# PL_DDR.net
KiCad netlist of a schematic drawn in Altium Designer
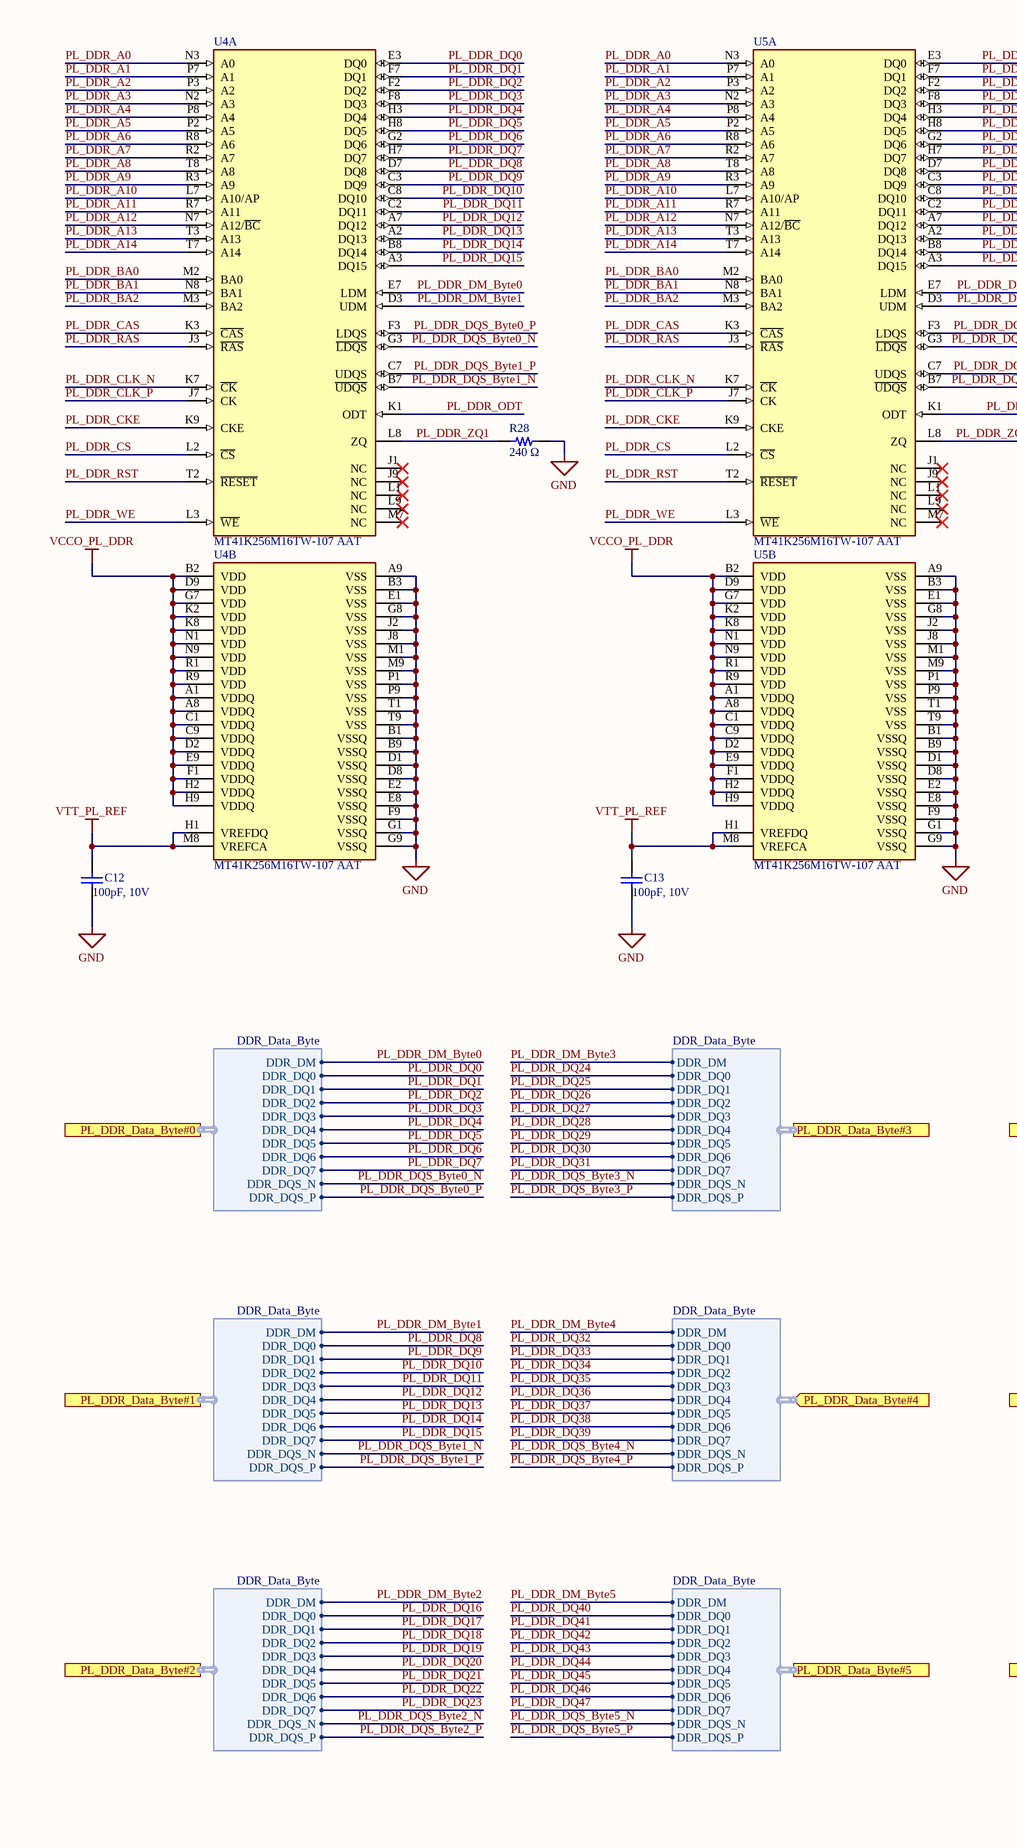
[diagram p0: PL_DDR.SchDoc, left]
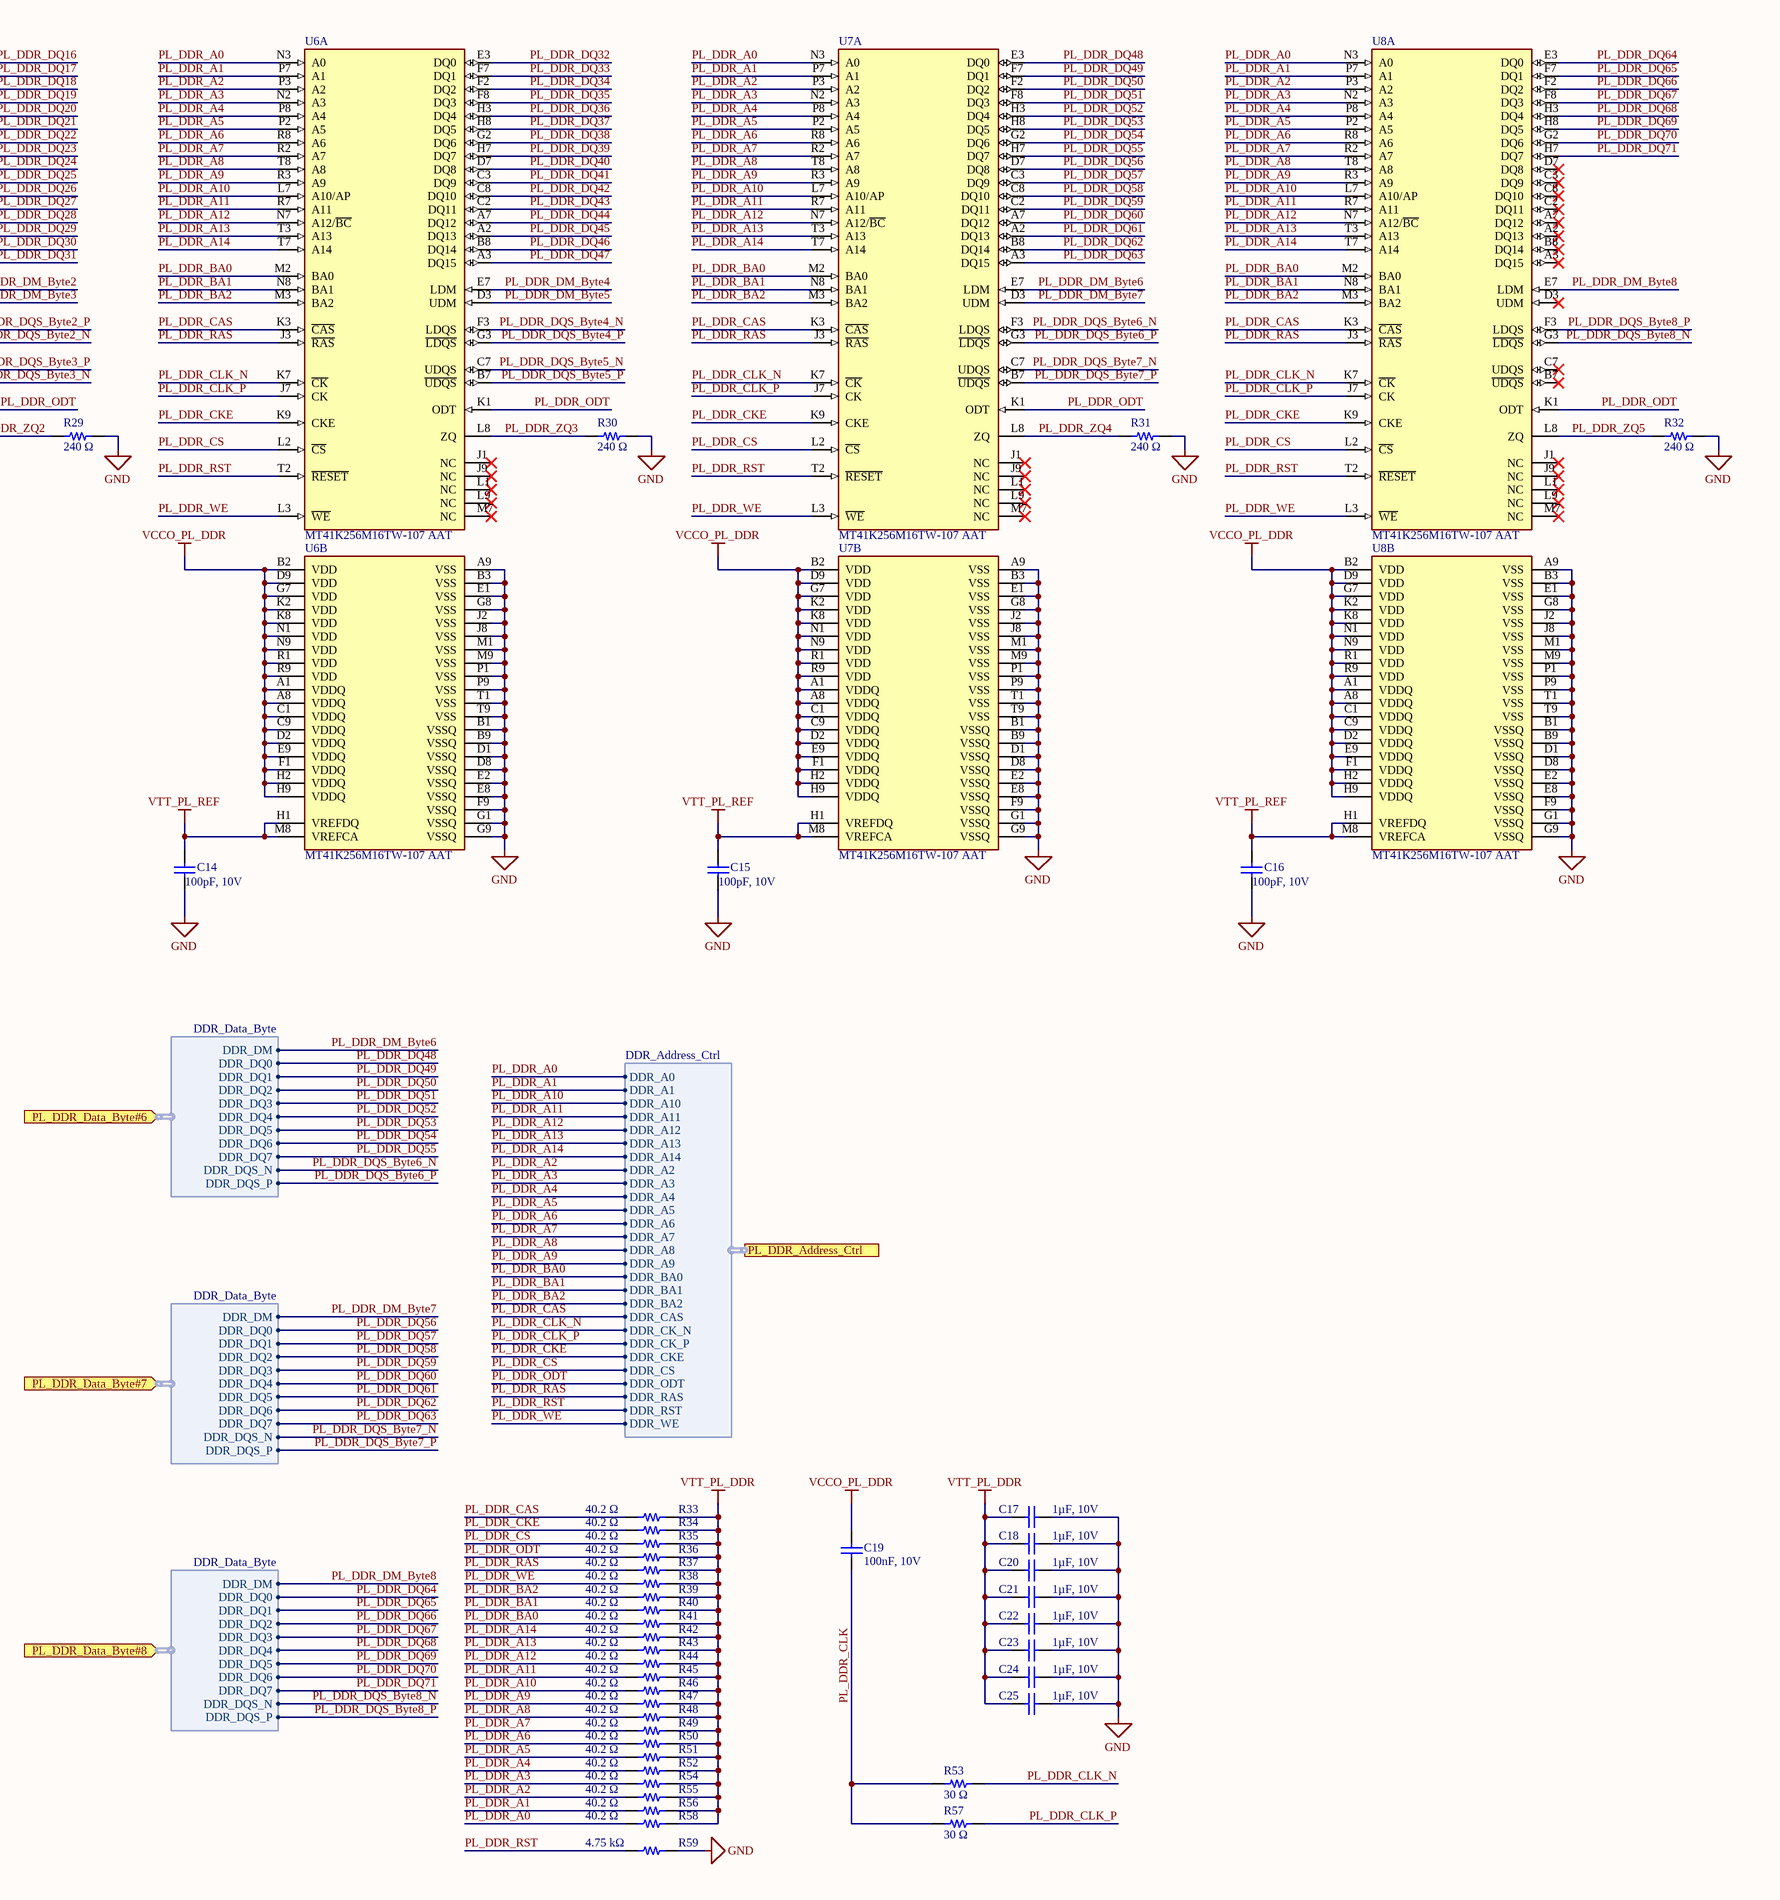
[diagram p1: PL_DDR.SchDoc, right]

(export (version "E")
  (design (tool "Eeschema 10.0.6"))
  (components
    (comp (ref "C12")
      (value "100pF, 10V")
      (footprint "WURTH_WCAP-CSGP_0402")
      (description "WCAP-CSGP Multilayer Ceramic Chip Capacitor, General Purpose, size 0402, NP0, 100pF, 10V")
      (fields
        (field (name "MANUFACTURER PART NUMBER") "885012005013")
        (field (name "MANUFACTURER") "Wurth Elektronik")
      )
      (libsource (lib "SpaceVNXBaseBoard") (part "885012005013"))
    )
    (comp (ref "C13")
      (value "100pF, 10V")
      (footprint "WURTH_WCAP-CSGP_0402")
      (description "WCAP-CSGP Multilayer Ceramic Chip Capacitor, General Purpose, size 0402, NP0, 100pF, 10V")
      (fields
        (field (name "MANUFACTURER PART NUMBER") "885012005013")
        (field (name "MANUFACTURER") "Wurth Elektronik")
      )
      (libsource (lib "SpaceVNXBaseBoard") (part "885012005013"))
    )
    (comp (ref "C14")
      (value "100pF, 10V")
      (footprint "WURTH_WCAP-CSGP_0402")
      (description "WCAP-CSGP Multilayer Ceramic Chip Capacitor, General Purpose, size 0402, NP0, 100pF, 10V")
      (fields
        (field (name "MANUFACTURER PART NUMBER") "885012005013")
        (field (name "MANUFACTURER") "Wurth Elektronik")
      )
      (libsource (lib "SpaceVNXBaseBoard") (part "885012005013"))
    )
    (comp (ref "C15")
      (value "100pF, 10V")
      (footprint "WURTH_WCAP-CSGP_0402")
      (description "WCAP-CSGP Multilayer Ceramic Chip Capacitor, General Purpose, size 0402, NP0, 100pF, 10V")
      (fields
        (field (name "MANUFACTURER PART NUMBER") "885012005013")
        (field (name "MANUFACTURER") "Wurth Elektronik")
      )
      (libsource (lib "SpaceVNXBaseBoard") (part "885012005013"))
    )
    (comp (ref "C16")
      (value "100pF, 10V")
      (footprint "WURTH_WCAP-CSGP_0402")
      (description "WCAP-CSGP Multilayer Ceramic Chip Capacitor, General Purpose, size 0402, NP0, 100pF, 10V")
      (fields
        (field (name "MANUFACTURER PART NUMBER") "885012005013")
        (field (name "MANUFACTURER") "Wurth Elektronik")
      )
      (libsource (lib "SpaceVNXBaseBoard") (part "885012005013"))
    )
    (comp (ref "C17")
      (value "1µF, 10V")
      (footprint "WURTH_WCAP-CSGP_0402")
      (description "WCAP-CSGP Multilayer Ceramic Chip Capacitor, General Purpose, size 0402, X5R, 1uF, 10V")
      (fields
        (field (name "MANUFACTURER PART NUMBER") "885012105012")
        (field (name "MANUFACTURER") "Wurth Elektronik")
      )
      (libsource (lib "SpaceVNXBaseBoard") (part "885012105012"))
    )
    (comp (ref "C18")
      (value "1µF, 10V")
      (footprint "WURTH_WCAP-CSGP_0402")
      (description "WCAP-CSGP Multilayer Ceramic Chip Capacitor, General Purpose, size 0402, X5R, 1uF, 10V")
      (fields
        (field (name "MANUFACTURER PART NUMBER") "885012105012")
        (field (name "MANUFACTURER") "Wurth Elektronik")
      )
      (libsource (lib "SpaceVNXBaseBoard") (part "885012105012"))
    )
    (comp (ref "C19")
      (value "100nF, 10V")
      (footprint "WURTH_WCAP-CSGP_0402")
      (description "WCAP-CSGP Multilayer Ceramic Chip Capacitor, General Purpose, size 0402, X7R, 100nF, 10V")
      (fields
        (field (name "MANUFACTURER PART NUMBER") "885012205018")
        (field (name "MANUFACTURER") "Wurth Elektronik")
      )
      (libsource (lib "SpaceVNXBaseBoard") (part "885012205018"))
    )
    (comp (ref "C20")
      (value "1µF, 10V")
      (footprint "WURTH_WCAP-CSGP_0402")
      (description "WCAP-CSGP Multilayer Ceramic Chip Capacitor, General Purpose, size 0402, X5R, 1uF, 10V")
      (fields
        (field (name "MANUFACTURER PART NUMBER") "885012105012")
        (field (name "MANUFACTURER") "Wurth Elektronik")
      )
      (libsource (lib "SpaceVNXBaseBoard") (part "885012105012"))
    )
    (comp (ref "C21")
      (value "1µF, 10V")
      (footprint "WURTH_WCAP-CSGP_0402")
      (description "WCAP-CSGP Multilayer Ceramic Chip Capacitor, General Purpose, size 0402, X5R, 1uF, 10V")
      (fields
        (field (name "MANUFACTURER PART NUMBER") "885012105012")
        (field (name "MANUFACTURER") "Wurth Elektronik")
      )
      (libsource (lib "SpaceVNXBaseBoard") (part "885012105012"))
    )
    (comp (ref "C22")
      (value "1µF, 10V")
      (footprint "WURTH_WCAP-CSGP_0402")
      (description "WCAP-CSGP Multilayer Ceramic Chip Capacitor, General Purpose, size 0402, X5R, 1uF, 10V")
      (fields
        (field (name "MANUFACTURER PART NUMBER") "885012105012")
        (field (name "MANUFACTURER") "Wurth Elektronik")
      )
      (libsource (lib "SpaceVNXBaseBoard") (part "885012105012"))
    )
    (comp (ref "C23")
      (value "1µF, 10V")
      (footprint "WURTH_WCAP-CSGP_0402")
      (description "WCAP-CSGP Multilayer Ceramic Chip Capacitor, General Purpose, size 0402, X5R, 1uF, 10V")
      (fields
        (field (name "MANUFACTURER PART NUMBER") "885012105012")
        (field (name "MANUFACTURER") "Wurth Elektronik")
      )
      (libsource (lib "SpaceVNXBaseBoard") (part "885012105012"))
    )
    (comp (ref "C24")
      (value "1µF, 10V")
      (footprint "WURTH_WCAP-CSGP_0402")
      (description "WCAP-CSGP Multilayer Ceramic Chip Capacitor, General Purpose, size 0402, X5R, 1uF, 10V")
      (fields
        (field (name "MANUFACTURER PART NUMBER") "885012105012")
        (field (name "MANUFACTURER") "Wurth Elektronik")
      )
      (libsource (lib "SpaceVNXBaseBoard") (part "885012105012"))
    )
    (comp (ref "C25")
      (value "1µF, 10V")
      (footprint "WURTH_WCAP-CSGP_0402")
      (description "WCAP-CSGP Multilayer Ceramic Chip Capacitor, General Purpose, size 0402, X5R, 1uF, 10V")
      (fields
        (field (name "MANUFACTURER PART NUMBER") "885012105012")
        (field (name "MANUFACTURER") "Wurth Elektronik")
      )
      (libsource (lib "SpaceVNXBaseBoard") (part "885012105012"))
    )
    (comp (ref "R28")
      (value "240 Ω")
      (footprint "PANASONIC_ERJ2G_0402")
      (description "General Purpose Thick Film Chip Resistors")
      (fields (field (name "MANUFACTURER") "Panasonic"))
      (libsource (lib "SpaceVNXBaseBoard") (part "ERJ2GEJ241X"))
    )
    (comp (ref "R29")
      (value "240 Ω")
      (footprint "PANASONIC_ERJ2G_0402")
      (description "General Purpose Thick Film Chip Resistors")
      (fields (field (name "MANUFACTURER") "Panasonic"))
      (libsource (lib "SpaceVNXBaseBoard") (part "ERJ2GEJ241X"))
    )
    (comp (ref "R30")
      (value "240 Ω")
      (footprint "PANASONIC_ERJ2G_0402")
      (description "General Purpose Thick Film Chip Resistors")
      (fields (field (name "MANUFACTURER") "Panasonic"))
      (libsource (lib "SpaceVNXBaseBoard") (part "ERJ2GEJ241X"))
    )
    (comp (ref "R31")
      (value "240 Ω")
      (footprint "PANASONIC_ERJ2G_0402")
      (description "General Purpose Thick Film Chip Resistors")
      (fields (field (name "MANUFACTURER") "Panasonic"))
      (libsource (lib "SpaceVNXBaseBoard") (part "ERJ2GEJ241X"))
    )
    (comp (ref "R32")
      (value "240 Ω")
      (footprint "PANASONIC_ERJ2G_0402")
      (description "General Purpose Thick Film Chip Resistors")
      (fields (field (name "MANUFACTURER") "Panasonic"))
      (libsource (lib "SpaceVNXBaseBoard") (part "ERJ2GEJ241X"))
    )
    (comp (ref "R33")
      (value "40.2 Ω")
      (footprint "PANASONIC_ERJ2G_0402")
      (description "General Purpose Thick Film Chip Resistors")
      (fields (field (name "MANUFACTURER") "Panasonic"))
      (libsource (lib "SpaceVNXBaseBoard") (part "ERJ2RKF40R2X"))
    )
    (comp (ref "R34")
      (value "40.2 Ω")
      (footprint "PANASONIC_ERJ2G_0402")
      (description "General Purpose Thick Film Chip Resistors")
      (fields (field (name "MANUFACTURER") "Panasonic"))
      (libsource (lib "SpaceVNXBaseBoard") (part "ERJ2RKF40R2X"))
    )
    (comp (ref "R35")
      (value "40.2 Ω")
      (footprint "PANASONIC_ERJ2G_0402")
      (description "General Purpose Thick Film Chip Resistors")
      (fields (field (name "MANUFACTURER") "Panasonic"))
      (libsource (lib "SpaceVNXBaseBoard") (part "ERJ2RKF40R2X"))
    )
    (comp (ref "R36")
      (value "40.2 Ω")
      (footprint "PANASONIC_ERJ2G_0402")
      (description "General Purpose Thick Film Chip Resistors")
      (fields (field (name "MANUFACTURER") "Panasonic"))
      (libsource (lib "SpaceVNXBaseBoard") (part "ERJ2RKF40R2X"))
    )
    (comp (ref "R37")
      (value "40.2 Ω")
      (footprint "PANASONIC_ERJ2G_0402")
      (description "General Purpose Thick Film Chip Resistors")
      (fields (field (name "MANUFACTURER") "Panasonic"))
      (libsource (lib "SpaceVNXBaseBoard") (part "ERJ2RKF40R2X"))
    )
    (comp (ref "R38")
      (value "40.2 Ω")
      (footprint "PANASONIC_ERJ2G_0402")
      (description "General Purpose Thick Film Chip Resistors")
      (fields (field (name "MANUFACTURER") "Panasonic"))
      (libsource (lib "SpaceVNXBaseBoard") (part "ERJ2RKF40R2X"))
    )
    (comp (ref "R39")
      (value "40.2 Ω")
      (footprint "PANASONIC_ERJ2G_0402")
      (description "General Purpose Thick Film Chip Resistors")
      (fields (field (name "MANUFACTURER") "Panasonic"))
      (libsource (lib "SpaceVNXBaseBoard") (part "ERJ2RKF40R2X"))
    )
    (comp (ref "R40")
      (value "40.2 Ω")
      (footprint "PANASONIC_ERJ2G_0402")
      (description "General Purpose Thick Film Chip Resistors")
      (fields (field (name "MANUFACTURER") "Panasonic"))
      (libsource (lib "SpaceVNXBaseBoard") (part "ERJ2RKF40R2X"))
    )
    (comp (ref "R41")
      (value "40.2 Ω")
      (footprint "PANASONIC_ERJ2G_0402")
      (description "General Purpose Thick Film Chip Resistors")
      (fields (field (name "MANUFACTURER") "Panasonic"))
      (libsource (lib "SpaceVNXBaseBoard") (part "ERJ2RKF40R2X"))
    )
    (comp (ref "R42")
      (value "40.2 Ω")
      (footprint "PANASONIC_ERJ2G_0402")
      (description "General Purpose Thick Film Chip Resistors")
      (fields (field (name "MANUFACTURER") "Panasonic"))
      (libsource (lib "SpaceVNXBaseBoard") (part "ERJ2RKF40R2X"))
    )
    (comp (ref "R43")
      (value "40.2 Ω")
      (footprint "PANASONIC_ERJ2G_0402")
      (description "General Purpose Thick Film Chip Resistors")
      (fields (field (name "MANUFACTURER") "Panasonic"))
      (libsource (lib "SpaceVNXBaseBoard") (part "ERJ2RKF40R2X"))
    )
    (comp (ref "R44")
      (value "40.2 Ω")
      (footprint "PANASONIC_ERJ2G_0402")
      (description "General Purpose Thick Film Chip Resistors")
      (fields (field (name "MANUFACTURER") "Panasonic"))
      (libsource (lib "SpaceVNXBaseBoard") (part "ERJ2RKF40R2X"))
    )
    (comp (ref "R45")
      (value "40.2 Ω")
      (footprint "PANASONIC_ERJ2G_0402")
      (description "General Purpose Thick Film Chip Resistors")
      (fields (field (name "MANUFACTURER") "Panasonic"))
      (libsource (lib "SpaceVNXBaseBoard") (part "ERJ2RKF40R2X"))
    )
    (comp (ref "R46")
      (value "40.2 Ω")
      (footprint "PANASONIC_ERJ2G_0402")
      (description "General Purpose Thick Film Chip Resistors")
      (fields (field (name "MANUFACTURER") "Panasonic"))
      (libsource (lib "SpaceVNXBaseBoard") (part "ERJ2RKF40R2X"))
    )
    (comp (ref "R47")
      (value "40.2 Ω")
      (footprint "PANASONIC_ERJ2G_0402")
      (description "General Purpose Thick Film Chip Resistors")
      (fields (field (name "MANUFACTURER") "Panasonic"))
      (libsource (lib "SpaceVNXBaseBoard") (part "ERJ2RKF40R2X"))
    )
    (comp (ref "R48")
      (value "40.2 Ω")
      (footprint "PANASONIC_ERJ2G_0402")
      (description "General Purpose Thick Film Chip Resistors")
      (fields (field (name "MANUFACTURER") "Panasonic"))
      (libsource (lib "SpaceVNXBaseBoard") (part "ERJ2RKF40R2X"))
    )
    (comp (ref "R49")
      (value "40.2 Ω")
      (footprint "PANASONIC_ERJ2G_0402")
      (description "General Purpose Thick Film Chip Resistors")
      (fields (field (name "MANUFACTURER") "Panasonic"))
      (libsource (lib "SpaceVNXBaseBoard") (part "ERJ2RKF40R2X"))
    )
    (comp (ref "R50")
      (value "40.2 Ω")
      (footprint "PANASONIC_ERJ2G_0402")
      (description "General Purpose Thick Film Chip Resistors")
      (fields (field (name "MANUFACTURER") "Panasonic"))
      (libsource (lib "SpaceVNXBaseBoard") (part "ERJ2RKF40R2X"))
    )
    (comp (ref "R51")
      (value "40.2 Ω")
      (footprint "PANASONIC_ERJ2G_0402")
      (description "General Purpose Thick Film Chip Resistors")
      (fields (field (name "MANUFACTURER") "Panasonic"))
      (libsource (lib "SpaceVNXBaseBoard") (part "ERJ2RKF40R2X"))
    )
    (comp (ref "R52")
      (value "40.2 Ω")
      (footprint "PANASONIC_ERJ2G_0402")
      (description "General Purpose Thick Film Chip Resistors")
      (fields (field (name "MANUFACTURER") "Panasonic"))
      (libsource (lib "SpaceVNXBaseBoard") (part "ERJ2RKF40R2X"))
    )
    (comp (ref "R53")
      (value "30 Ω")
      (footprint "PANASONIC_ERJ2G_0402")
      (description "General Purpose Thick Film Chip Resistors")
      (fields (field (name "MANUFACTURER") "Panasonic"))
      (libsource (lib "SpaceVNXBaseBoard") (part "ERJ2GEJ300X"))
    )
    (comp (ref "R54")
      (value "40.2 Ω")
      (footprint "PANASONIC_ERJ2G_0402")
      (description "General Purpose Thick Film Chip Resistors")
      (fields (field (name "MANUFACTURER") "Panasonic"))
      (libsource (lib "SpaceVNXBaseBoard") (part "ERJ2RKF40R2X"))
    )
    (comp (ref "R55")
      (value "40.2 Ω")
      (footprint "PANASONIC_ERJ2G_0402")
      (description "General Purpose Thick Film Chip Resistors")
      (fields (field (name "MANUFACTURER") "Panasonic"))
      (libsource (lib "SpaceVNXBaseBoard") (part "ERJ2RKF40R2X"))
    )
    (comp (ref "R56")
      (value "40.2 Ω")
      (footprint "PANASONIC_ERJ2G_0402")
      (description "General Purpose Thick Film Chip Resistors")
      (fields (field (name "MANUFACTURER") "Panasonic"))
      (libsource (lib "SpaceVNXBaseBoard") (part "ERJ2RKF40R2X"))
    )
    (comp (ref "R57")
      (value "30 Ω")
      (footprint "PANASONIC_ERJ2G_0402")
      (description "General Purpose Thick Film Chip Resistors")
      (fields (field (name "MANUFACTURER") "Panasonic"))
      (libsource (lib "SpaceVNXBaseBoard") (part "ERJ2GEJ300X"))
    )
    (comp (ref "R58")
      (value "40.2 Ω")
      (footprint "PANASONIC_ERJ2G_0402")
      (description "General Purpose Thick Film Chip Resistors")
      (fields (field (name "MANUFACTURER") "Panasonic"))
      (libsource (lib "SpaceVNXBaseBoard") (part "ERJ2RKF40R2X"))
    )
    (comp (ref "R59")
      (value "4.75 kΩ")
      (footprint "PANASONIC_ERJ2G_0402")
      (description "General Purpose Thick Film Chip Resistors")
      (fields (field (name "MANUFACTURER") "Panasonic"))
      (libsource (lib "SpaceVNXBaseBoard") (part "ERJ2RKF4751X"))
    )
    (comp (ref "U4")
      (value "MT41K256M16TW-107 AAT")
      (footprint "Micron_TW")
      (description "DDR3L SDRAM")
      (libsource (lib "SpaceVNXBaseBoard") (part "MT41K256M16TW-107 AAT"))
    )
    (comp (ref "U5")
      (value "MT41K256M16TW-107 AAT")
      (footprint "Micron_TW")
      (description "DDR3L SDRAM")
      (libsource (lib "SpaceVNXBaseBoard") (part "MT41K256M16TW-107 AAT"))
    )
    (comp (ref "U6")
      (value "MT41K256M16TW-107 AAT")
      (footprint "Micron_TW")
      (description "DDR3L SDRAM")
      (libsource (lib "SpaceVNXBaseBoard") (part "MT41K256M16TW-107 AAT"))
    )
    (comp (ref "U7")
      (value "MT41K256M16TW-107 AAT")
      (footprint "Micron_TW")
      (description "DDR3L SDRAM")
      (libsource (lib "SpaceVNXBaseBoard") (part "MT41K256M16TW-107 AAT"))
    )
    (comp (ref "U8")
      (value "MT41K256M16TW-107 AAT")
      (footprint "Micron_TW")
      (description "DDR3L SDRAM")
      (libsource (lib "SpaceVNXBaseBoard") (part "MT41K256M16TW-107 AAT"))
    )
  )
  (nets
    (net (code "3") (name "/PL_DDR_A0") (class "Default")
      (node (ref "R58") (pin "1") (pinfunction "1_1") (pintype "passive"))
      (node (ref "U4") (pin "N3") (pinfunction "A0_N3") (pintype "input"))
      (node (ref "U5") (pin "N3") (pinfunction "A0_N3") (pintype "input"))
      (node (ref "U6") (pin "N3") (pinfunction "A0_N3") (pintype "input"))
      (node (ref "U7") (pin "N3") (pinfunction "A0_N3") (pintype "input"))
      (node (ref "U8") (pin "N3") (pinfunction "A0_N3") (pintype "input"))
    )
    (net (code "4") (name "/PL_DDR_A1") (class "Default")
      (node (ref "R56") (pin "1") (pinfunction "1_1") (pintype "passive"))
      (node (ref "U4") (pin "P7") (pinfunction "A1_P7") (pintype "input"))
      (node (ref "U5") (pin "P7") (pinfunction "A1_P7") (pintype "input"))
      (node (ref "U6") (pin "P7") (pinfunction "A1_P7") (pintype "input"))
      (node (ref "U7") (pin "P7") (pinfunction "A1_P7") (pintype "input"))
      (node (ref "U8") (pin "P7") (pinfunction "A1_P7") (pintype "input"))
    )
    (net (code "5") (name "/PL_DDR_A2") (class "Default")
      (node (ref "R55") (pin "1") (pinfunction "1_1") (pintype "passive"))
      (node (ref "U4") (pin "P3") (pinfunction "A2_P3") (pintype "input"))
      (node (ref "U5") (pin "P3") (pinfunction "A2_P3") (pintype "input"))
      (node (ref "U6") (pin "P3") (pinfunction "A2_P3") (pintype "input"))
      (node (ref "U7") (pin "P3") (pinfunction "A2_P3") (pintype "input"))
      (node (ref "U8") (pin "P3") (pinfunction "A2_P3") (pintype "input"))
    )
    (net (code "6") (name "/PL_DDR_A3") (class "Default")
      (node (ref "R54") (pin "1") (pinfunction "1_1") (pintype "passive"))
      (node (ref "U4") (pin "N2") (pinfunction "A3_N2") (pintype "input"))
      (node (ref "U5") (pin "N2") (pinfunction "A3_N2") (pintype "input"))
      (node (ref "U6") (pin "N2") (pinfunction "A3_N2") (pintype "input"))
      (node (ref "U7") (pin "N2") (pinfunction "A3_N2") (pintype "input"))
      (node (ref "U8") (pin "N2") (pinfunction "A3_N2") (pintype "input"))
    )
    (net (code "7") (name "/PL_DDR_A4") (class "Default")
      (node (ref "R52") (pin "1") (pinfunction "1_1") (pintype "passive"))
      (node (ref "U4") (pin "P8") (pinfunction "A4_P8") (pintype "input"))
      (node (ref "U5") (pin "P8") (pinfunction "A4_P8") (pintype "input"))
      (node (ref "U6") (pin "P8") (pinfunction "A4_P8") (pintype "input"))
      (node (ref "U7") (pin "P8") (pinfunction "A4_P8") (pintype "input"))
      (node (ref "U8") (pin "P8") (pinfunction "A4_P8") (pintype "input"))
    )
    (net (code "8") (name "/PL_DDR_A5") (class "Default")
      (node (ref "R51") (pin "1") (pinfunction "1_1") (pintype "passive"))
      (node (ref "U4") (pin "P2") (pinfunction "A5_P2") (pintype "input"))
      (node (ref "U5") (pin "P2") (pinfunction "A5_P2") (pintype "input"))
      (node (ref "U6") (pin "P2") (pinfunction "A5_P2") (pintype "input"))
      (node (ref "U7") (pin "P2") (pinfunction "A5_P2") (pintype "input"))
      (node (ref "U8") (pin "P2") (pinfunction "A5_P2") (pintype "input"))
    )
    (net (code "9") (name "/PL_DDR_A6") (class "Default")
      (node (ref "R50") (pin "1") (pinfunction "1_1") (pintype "passive"))
      (node (ref "U4") (pin "R8") (pinfunction "A6_R8") (pintype "input"))
      (node (ref "U5") (pin "R8") (pinfunction "A6_R8") (pintype "input"))
      (node (ref "U6") (pin "R8") (pinfunction "A6_R8") (pintype "input"))
      (node (ref "U7") (pin "R8") (pinfunction "A6_R8") (pintype "input"))
      (node (ref "U8") (pin "R8") (pinfunction "A6_R8") (pintype "input"))
    )
    (net (code "10") (name "/PL_DDR_A7") (class "Default")
      (node (ref "R49") (pin "1") (pinfunction "1_1") (pintype "passive"))
      (node (ref "U4") (pin "R2") (pinfunction "A7_R2") (pintype "input"))
      (node (ref "U5") (pin "R2") (pinfunction "A7_R2") (pintype "input"))
      (node (ref "U6") (pin "R2") (pinfunction "A7_R2") (pintype "input"))
      (node (ref "U7") (pin "R2") (pinfunction "A7_R2") (pintype "input"))
      (node (ref "U8") (pin "R2") (pinfunction "A7_R2") (pintype "input"))
    )
    (net (code "11") (name "/PL_DDR_A8") (class "Default")
      (node (ref "R48") (pin "1") (pinfunction "1_1") (pintype "passive"))
      (node (ref "U4") (pin "T8") (pinfunction "A8_T8") (pintype "input"))
      (node (ref "U5") (pin "T8") (pinfunction "A8_T8") (pintype "input"))
      (node (ref "U6") (pin "T8") (pinfunction "A8_T8") (pintype "input"))
      (node (ref "U7") (pin "T8") (pinfunction "A8_T8") (pintype "input"))
      (node (ref "U8") (pin "T8") (pinfunction "A8_T8") (pintype "input"))
    )
    (net (code "12") (name "/PL_DDR_A9") (class "Default")
      (node (ref "R47") (pin "1") (pinfunction "1_1") (pintype "passive"))
      (node (ref "U4") (pin "R3") (pinfunction "A9_R3") (pintype "input"))
      (node (ref "U5") (pin "R3") (pinfunction "A9_R3") (pintype "input"))
      (node (ref "U6") (pin "R3") (pinfunction "A9_R3") (pintype "input"))
      (node (ref "U7") (pin "R3") (pinfunction "A9_R3") (pintype "input"))
      (node (ref "U8") (pin "R3") (pinfunction "A9_R3") (pintype "input"))
    )
    (net (code "13") (name "/PL_DDR_A10") (class "Default")
      (node (ref "R46") (pin "1") (pinfunction "1_1") (pintype "passive"))
      (node (ref "U4") (pin "L7") (pinfunction "A10/AP_L7") (pintype "input"))
      (node (ref "U5") (pin "L7") (pinfunction "A10/AP_L7") (pintype "input"))
      (node (ref "U6") (pin "L7") (pinfunction "A10/AP_L7") (pintype "input"))
      (node (ref "U7") (pin "L7") (pinfunction "A10/AP_L7") (pintype "input"))
      (node (ref "U8") (pin "L7") (pinfunction "A10/AP_L7") (pintype "input"))
    )
    (net (code "14") (name "/PL_DDR_A11") (class "Default")
      (node (ref "R45") (pin "1") (pinfunction "1_1") (pintype "passive"))
      (node (ref "U4") (pin "R7") (pinfunction "A11_R7") (pintype "input"))
      (node (ref "U5") (pin "R7") (pinfunction "A11_R7") (pintype "input"))
      (node (ref "U6") (pin "R7") (pinfunction "A11_R7") (pintype "input"))
      (node (ref "U7") (pin "R7") (pinfunction "A11_R7") (pintype "input"))
      (node (ref "U8") (pin "R7") (pinfunction "A11_R7") (pintype "input"))
    )
    (net (code "15") (name "/PL_DDR_A12") (class "Default")
      (node (ref "R44") (pin "1") (pinfunction "1_1") (pintype "passive"))
      (node (ref "U4") (pin "N7") (pinfunction "A12/~{BC}_N7") (pintype "input"))
      (node (ref "U5") (pin "N7") (pinfunction "A12/~{BC}_N7") (pintype "input"))
      (node (ref "U6") (pin "N7") (pinfunction "A12/~{BC}_N7") (pintype "input"))
      (node (ref "U7") (pin "N7") (pinfunction "A12/~{BC}_N7") (pintype "input"))
      (node (ref "U8") (pin "N7") (pinfunction "A12/~{BC}_N7") (pintype "input"))
    )
    (net (code "16") (name "/PL_DDR_A13") (class "Default")
      (node (ref "R43") (pin "1") (pinfunction "1_1") (pintype "passive"))
      (node (ref "U4") (pin "T3") (pinfunction "A13_T3") (pintype "input"))
      (node (ref "U5") (pin "T3") (pinfunction "A13_T3") (pintype "input"))
      (node (ref "U6") (pin "T3") (pinfunction "A13_T3") (pintype "input"))
      (node (ref "U7") (pin "T3") (pinfunction "A13_T3") (pintype "input"))
      (node (ref "U8") (pin "T3") (pinfunction "A13_T3") (pintype "input"))
    )
    (net (code "17") (name "/PL_DDR_A14") (class "Default")
      (node (ref "R42") (pin "1") (pinfunction "1_1") (pintype "passive"))
      (node (ref "U4") (pin "T7") (pinfunction "A14_T7") (pintype "input"))
      (node (ref "U5") (pin "T7") (pinfunction "A14_T7") (pintype "input"))
      (node (ref "U6") (pin "T7") (pinfunction "A14_T7") (pintype "input"))
      (node (ref "U7") (pin "T7") (pinfunction "A14_T7") (pintype "input"))
      (node (ref "U8") (pin "T7") (pinfunction "A14_T7") (pintype "input"))
    )
    (net (code "18") (name "/PL_DDR_BA0") (class "Default")
      (node (ref "R41") (pin "1") (pinfunction "1_1") (pintype "passive"))
      (node (ref "U4") (pin "M2") (pinfunction "BA0_M2") (pintype "input"))
      (node (ref "U5") (pin "M2") (pinfunction "BA0_M2") (pintype "input"))
      (node (ref "U6") (pin "M2") (pinfunction "BA0_M2") (pintype "input"))
      (node (ref "U7") (pin "M2") (pinfunction "BA0_M2") (pintype "input"))
      (node (ref "U8") (pin "M2") (pinfunction "BA0_M2") (pintype "input"))
    )
    (net (code "19") (name "/PL_DDR_BA1") (class "Default")
      (node (ref "R40") (pin "1") (pinfunction "1_1") (pintype "passive"))
      (node (ref "U4") (pin "N8") (pinfunction "BA1_N8") (pintype "input"))
      (node (ref "U5") (pin "N8") (pinfunction "BA1_N8") (pintype "input"))
      (node (ref "U6") (pin "N8") (pinfunction "BA1_N8") (pintype "input"))
      (node (ref "U7") (pin "N8") (pinfunction "BA1_N8") (pintype "input"))
      (node (ref "U8") (pin "N8") (pinfunction "BA1_N8") (pintype "input"))
    )
    (net (code "20") (name "/PL_DDR_BA2") (class "Default")
      (node (ref "R39") (pin "1") (pinfunction "1_1") (pintype "passive"))
      (node (ref "U4") (pin "M3") (pinfunction "BA2_M3") (pintype "input"))
      (node (ref "U5") (pin "M3") (pinfunction "BA2_M3") (pintype "input"))
      (node (ref "U6") (pin "M3") (pinfunction "BA2_M3") (pintype "input"))
      (node (ref "U7") (pin "M3") (pinfunction "BA2_M3") (pintype "input"))
      (node (ref "U8") (pin "M3") (pinfunction "BA2_M3") (pintype "input"))
    )
    (net (code "21") (name "/PL_DDR_CAS") (class "Default")
      (node (ref "R33") (pin "1") (pinfunction "1_1") (pintype "passive"))
      (node (ref "U4") (pin "K3") (pinfunction "~{CAS}_K3") (pintype "input"))
      (node (ref "U5") (pin "K3") (pinfunction "~{CAS}_K3") (pintype "input"))
      (node (ref "U6") (pin "K3") (pinfunction "~{CAS}_K3") (pintype "input"))
      (node (ref "U7") (pin "K3") (pinfunction "~{CAS}_K3") (pintype "input"))
      (node (ref "U8") (pin "K3") (pinfunction "~{CAS}_K3") (pintype "input"))
    )
    (net (code "22") (name "/PL_DDR_CKE") (class "Default")
      (node (ref "R34") (pin "1") (pinfunction "1_1") (pintype "passive"))
      (node (ref "U4") (pin "K9") (pinfunction "CKE_K9") (pintype "input"))
      (node (ref "U5") (pin "K9") (pinfunction "CKE_K9") (pintype "input"))
      (node (ref "U6") (pin "K9") (pinfunction "CKE_K9") (pintype "input"))
      (node (ref "U7") (pin "K9") (pinfunction "CKE_K9") (pintype "input"))
      (node (ref "U8") (pin "K9") (pinfunction "CKE_K9") (pintype "input"))
    )
    (net (code "23") (name "/PL_DDR_CLK") (class "Default")
      (node (ref "C19") (pin "1") (pinfunction "1_1") (pintype "passive"))
      (node (ref "R53") (pin "2") (pinfunction "2_2") (pintype "passive"))
      (node (ref "R57") (pin "2") (pinfunction "2_2") (pintype "passive"))
    )
    (net (code "24") (name "/PL_DDR_CLK_N") (class "Default")
      (node (ref "R53") (pin "1") (pinfunction "1_1") (pintype "passive"))
      (node (ref "U4") (pin "K7") (pinfunction "~{CK}_K7") (pintype "input"))
      (node (ref "U5") (pin "K7") (pinfunction "~{CK}_K7") (pintype "input"))
      (node (ref "U6") (pin "K7") (pinfunction "~{CK}_K7") (pintype "input"))
      (node (ref "U7") (pin "K7") (pinfunction "~{CK}_K7") (pintype "input"))
      (node (ref "U8") (pin "K7") (pinfunction "~{CK}_K7") (pintype "input"))
    )
    (net (code "25") (name "/PL_DDR_CLK_P") (class "Default")
      (node (ref "R57") (pin "1") (pinfunction "1_1") (pintype "passive"))
      (node (ref "U4") (pin "J7") (pinfunction "CK_J7") (pintype "input"))
      (node (ref "U5") (pin "J7") (pinfunction "CK_J7") (pintype "input"))
      (node (ref "U6") (pin "J7") (pinfunction "CK_J7") (pintype "input"))
      (node (ref "U7") (pin "J7") (pinfunction "CK_J7") (pintype "input"))
      (node (ref "U8") (pin "J7") (pinfunction "CK_J7") (pintype "input"))
    )
    (net (code "26") (name "/PL_DDR_CS") (class "Default")
      (node (ref "R35") (pin "1") (pinfunction "1_1") (pintype "passive"))
      (node (ref "U4") (pin "L2") (pinfunction "~{CS}_L2") (pintype "input"))
      (node (ref "U5") (pin "L2") (pinfunction "~{CS}_L2") (pintype "input"))
      (node (ref "U6") (pin "L2") (pinfunction "~{CS}_L2") (pintype "input"))
      (node (ref "U7") (pin "L2") (pinfunction "~{CS}_L2") (pintype "input"))
      (node (ref "U8") (pin "L2") (pinfunction "~{CS}_L2") (pintype "input"))
    )
    (net (code "27") (name "/PL_DDR_DM_Byte0") (class "Default")
      (node (ref "U4") (pin "E7") (pinfunction "LDM_E7") (pintype "input"))
    )
    (net (code "28") (name "/PL_DDR_DM_Byte1") (class "Default")
      (node (ref "U4") (pin "D3") (pinfunction "UDM_D3") (pintype "input"))
    )
    (net (code "29") (name "/PL_DDR_DM_Byte2") (class "Default")
      (node (ref "U5") (pin "E7") (pinfunction "LDM_E7") (pintype "input"))
    )
    (net (code "30") (name "/PL_DDR_DM_Byte3") (class "Default")
      (node (ref "U5") (pin "D3") (pinfunction "UDM_D3") (pintype "input"))
    )
    (net (code "31") (name "/PL_DDR_DM_Byte4") (class "Default")
      (node (ref "U6") (pin "E7") (pinfunction "LDM_E7") (pintype "input"))
    )
    (net (code "32") (name "/PL_DDR_DM_Byte5") (class "Default")
      (node (ref "U6") (pin "D3") (pinfunction "UDM_D3") (pintype "input"))
    )
    (net (code "33") (name "/PL_DDR_DM_Byte6") (class "Default")
      (node (ref "U7") (pin "E7") (pinfunction "LDM_E7") (pintype "input"))
    )
    (net (code "34") (name "/PL_DDR_DM_Byte7") (class "Default")
      (node (ref "U7") (pin "D3") (pinfunction "UDM_D3") (pintype "input"))
    )
    (net (code "35") (name "/PL_DDR_DM_Byte8") (class "Default")
      (node (ref "U8") (pin "E7") (pinfunction "LDM_E7") (pintype "input"))
    )
    (net (code "36") (name "/PL_DDR_DQ0") (class "Default")
      (node (ref "U4") (pin "E3") (pinfunction "DQ0_E3") (pintype "bidirectional"))
    )
    (net (code "37") (name "/PL_DDR_DQ1") (class "Default")
      (node (ref "U4") (pin "F7") (pinfunction "DQ1_F7") (pintype "bidirectional"))
    )
    (net (code "38") (name "/PL_DDR_DQ2") (class "Default")
      (node (ref "U4") (pin "F2") (pinfunction "DQ2_F2") (pintype "bidirectional"))
    )
    (net (code "39") (name "/PL_DDR_DQ3") (class "Default")
      (node (ref "U4") (pin "F8") (pinfunction "DQ3_F8") (pintype "bidirectional"))
    )
    (net (code "40") (name "/PL_DDR_DQ4") (class "Default")
      (node (ref "U4") (pin "H3") (pinfunction "DQ4_H3") (pintype "bidirectional"))
    )
    (net (code "41") (name "/PL_DDR_DQ5") (class "Default")
      (node (ref "U4") (pin "H8") (pinfunction "DQ5_H8") (pintype "bidirectional"))
    )
    (net (code "42") (name "/PL_DDR_DQ6") (class "Default")
      (node (ref "U4") (pin "G2") (pinfunction "DQ6_G2") (pintype "bidirectional"))
    )
    (net (code "43") (name "/PL_DDR_DQ7") (class "Default")
      (node (ref "U4") (pin "H7") (pinfunction "DQ7_H7") (pintype "bidirectional"))
    )
    (net (code "44") (name "/PL_DDR_DQ8") (class "Default")
      (node (ref "U4") (pin "D7") (pinfunction "DQ8_D7") (pintype "bidirectional"))
    )
    (net (code "45") (name "/PL_DDR_DQ9") (class "Default")
      (node (ref "U4") (pin "C3") (pinfunction "DQ9_C3") (pintype "bidirectional"))
    )
    (net (code "46") (name "/PL_DDR_DQ10") (class "Default")
      (node (ref "U4") (pin "C8") (pinfunction "DQ10_C8") (pintype "bidirectional"))
    )
    (net (code "47") (name "/PL_DDR_DQ11") (class "Default")
      (node (ref "U4") (pin "C2") (pinfunction "DQ11_C2") (pintype "bidirectional"))
    )
    (net (code "48") (name "/PL_DDR_DQ12") (class "Default")
      (node (ref "U4") (pin "A7") (pinfunction "DQ12_A7") (pintype "bidirectional"))
    )
    (net (code "49") (name "/PL_DDR_DQ13") (class "Default")
      (node (ref "U4") (pin "A2") (pinfunction "DQ13_A2") (pintype "bidirectional"))
    )
    (net (code "50") (name "/PL_DDR_DQ14") (class "Default")
      (node (ref "U4") (pin "B8") (pinfunction "DQ14_B8") (pintype "bidirectional"))
    )
    (net (code "51") (name "/PL_DDR_DQ15") (class "Default")
      (node (ref "U4") (pin "A3") (pinfunction "DQ15_A3") (pintype "bidirectional"))
    )
    (net (code "52") (name "/PL_DDR_DQ16") (class "Default")
      (node (ref "U5") (pin "E3") (pinfunction "DQ0_E3") (pintype "bidirectional"))
    )
    (net (code "53") (name "/PL_DDR_DQ17") (class "Default")
      (node (ref "U5") (pin "F7") (pinfunction "DQ1_F7") (pintype "bidirectional"))
    )
    (net (code "54") (name "/PL_DDR_DQ18") (class "Default")
      (node (ref "U5") (pin "F2") (pinfunction "DQ2_F2") (pintype "bidirectional"))
    )
    (net (code "55") (name "/PL_DDR_DQ19") (class "Default")
      (node (ref "U5") (pin "F8") (pinfunction "DQ3_F8") (pintype "bidirectional"))
    )
    (net (code "56") (name "/PL_DDR_DQ20") (class "Default")
      (node (ref "U5") (pin "H3") (pinfunction "DQ4_H3") (pintype "bidirectional"))
    )
    (net (code "57") (name "/PL_DDR_DQ21") (class "Default")
      (node (ref "U5") (pin "H8") (pinfunction "DQ5_H8") (pintype "bidirectional"))
    )
    (net (code "58") (name "/PL_DDR_DQ22") (class "Default")
      (node (ref "U5") (pin "G2") (pinfunction "DQ6_G2") (pintype "bidirectional"))
    )
    (net (code "59") (name "/PL_DDR_DQ23") (class "Default")
      (node (ref "U5") (pin "H7") (pinfunction "DQ7_H7") (pintype "bidirectional"))
    )
    (net (code "60") (name "/PL_DDR_DQ24") (class "Default")
      (node (ref "U5") (pin "D7") (pinfunction "DQ8_D7") (pintype "bidirectional"))
    )
    (net (code "61") (name "/PL_DDR_DQ25") (class "Default")
      (node (ref "U5") (pin "C3") (pinfunction "DQ9_C3") (pintype "bidirectional"))
    )
    (net (code "62") (name "/PL_DDR_DQ26") (class "Default")
      (node (ref "U5") (pin "C8") (pinfunction "DQ10_C8") (pintype "bidirectional"))
    )
    (net (code "63") (name "/PL_DDR_DQ27") (class "Default")
      (node (ref "U5") (pin "C2") (pinfunction "DQ11_C2") (pintype "bidirectional"))
    )
    (net (code "64") (name "/PL_DDR_DQ28") (class "Default")
      (node (ref "U5") (pin "A7") (pinfunction "DQ12_A7") (pintype "bidirectional"))
    )
    (net (code "65") (name "/PL_DDR_DQ29") (class "Default")
      (node (ref "U5") (pin "A2") (pinfunction "DQ13_A2") (pintype "bidirectional"))
    )
    (net (code "66") (name "/PL_DDR_DQ30") (class "Default")
      (node (ref "U5") (pin "B8") (pinfunction "DQ14_B8") (pintype "bidirectional"))
    )
    (net (code "67") (name "/PL_DDR_DQ31") (class "Default")
      (node (ref "U5") (pin "A3") (pinfunction "DQ15_A3") (pintype "bidirectional"))
    )
    (net (code "68") (name "/PL_DDR_DQ32") (class "Default")
      (node (ref "U6") (pin "E3") (pinfunction "DQ0_E3") (pintype "bidirectional"))
    )
    (net (code "69") (name "/PL_DDR_DQ33") (class "Default")
      (node (ref "U6") (pin "F7") (pinfunction "DQ1_F7") (pintype "bidirectional"))
    )
    (net (code "70") (name "/PL_DDR_DQ34") (class "Default")
      (node (ref "U6") (pin "F2") (pinfunction "DQ2_F2") (pintype "bidirectional"))
    )
    (net (code "71") (name "/PL_DDR_DQ35") (class "Default")
      (node (ref "U6") (pin "F8") (pinfunction "DQ3_F8") (pintype "bidirectional"))
    )
    (net (code "72") (name "/PL_DDR_DQ36") (class "Default")
      (node (ref "U6") (pin "H3") (pinfunction "DQ4_H3") (pintype "bidirectional"))
    )
    (net (code "73") (name "/PL_DDR_DQ37") (class "Default")
      (node (ref "U6") (pin "H8") (pinfunction "DQ5_H8") (pintype "bidirectional"))
    )
    (net (code "74") (name "/PL_DDR_DQ38") (class "Default")
      (node (ref "U6") (pin "G2") (pinfunction "DQ6_G2") (pintype "bidirectional"))
    )
    (net (code "75") (name "/PL_DDR_DQ39") (class "Default")
      (node (ref "U6") (pin "H7") (pinfunction "DQ7_H7") (pintype "bidirectional"))
    )
    (net (code "76") (name "/PL_DDR_DQ40") (class "Default")
      (node (ref "U6") (pin "D7") (pinfunction "DQ8_D7") (pintype "bidirectional"))
    )
    (net (code "77") (name "/PL_DDR_DQ41") (class "Default")
      (node (ref "U6") (pin "C3") (pinfunction "DQ9_C3") (pintype "bidirectional"))
    )
    (net (code "78") (name "/PL_DDR_DQ42") (class "Default")
      (node (ref "U6") (pin "C8") (pinfunction "DQ10_C8") (pintype "bidirectional"))
    )
    (net (code "79") (name "/PL_DDR_DQ43") (class "Default")
      (node (ref "U6") (pin "C2") (pinfunction "DQ11_C2") (pintype "bidirectional"))
    )
    (net (code "80") (name "/PL_DDR_DQ44") (class "Default")
      (node (ref "U6") (pin "A7") (pinfunction "DQ12_A7") (pintype "bidirectional"))
    )
    (net (code "81") (name "/PL_DDR_DQ45") (class "Default")
      (node (ref "U6") (pin "A2") (pinfunction "DQ13_A2") (pintype "bidirectional"))
    )
    (net (code "82") (name "/PL_DDR_DQ46") (class "Default")
      (node (ref "U6") (pin "B8") (pinfunction "DQ14_B8") (pintype "bidirectional"))
    )
    (net (code "83") (name "/PL_DDR_DQ47") (class "Default")
      (node (ref "U6") (pin "A3") (pinfunction "DQ15_A3") (pintype "bidirectional"))
    )
    (net (code "84") (name "/PL_DDR_DQ48") (class "Default")
      (node (ref "U7") (pin "E3") (pinfunction "DQ0_E3") (pintype "bidirectional"))
    )
    (net (code "85") (name "/PL_DDR_DQ49") (class "Default")
      (node (ref "U7") (pin "F7") (pinfunction "DQ1_F7") (pintype "bidirectional"))
    )
    (net (code "86") (name "/PL_DDR_DQ50") (class "Default")
      (node (ref "U7") (pin "F2") (pinfunction "DQ2_F2") (pintype "bidirectional"))
    )
    (net (code "87") (name "/PL_DDR_DQ51") (class "Default")
      (node (ref "U7") (pin "F8") (pinfunction "DQ3_F8") (pintype "bidirectional"))
    )
    (net (code "88") (name "/PL_DDR_DQ52") (class "Default")
      (node (ref "U7") (pin "H3") (pinfunction "DQ4_H3") (pintype "bidirectional"))
    )
    (net (code "89") (name "/PL_DDR_DQ53") (class "Default")
      (node (ref "U7") (pin "H8") (pinfunction "DQ5_H8") (pintype "bidirectional"))
    )
    (net (code "90") (name "/PL_DDR_DQ54") (class "Default")
      (node (ref "U7") (pin "G2") (pinfunction "DQ6_G2") (pintype "bidirectional"))
    )
    (net (code "91") (name "/PL_DDR_DQ55") (class "Default")
      (node (ref "U7") (pin "H7") (pinfunction "DQ7_H7") (pintype "bidirectional"))
    )
    (net (code "92") (name "/PL_DDR_DQ56") (class "Default")
      (node (ref "U7") (pin "D7") (pinfunction "DQ8_D7") (pintype "bidirectional"))
    )
    (net (code "93") (name "/PL_DDR_DQ57") (class "Default")
      (node (ref "U7") (pin "C3") (pinfunction "DQ9_C3") (pintype "bidirectional"))
    )
    (net (code "94") (name "/PL_DDR_DQ58") (class "Default")
      (node (ref "U7") (pin "C8") (pinfunction "DQ10_C8") (pintype "bidirectional"))
    )
    (net (code "95") (name "/PL_DDR_DQ59") (class "Default")
      (node (ref "U7") (pin "C2") (pinfunction "DQ11_C2") (pintype "bidirectional"))
    )
    (net (code "96") (name "/PL_DDR_DQ60") (class "Default")
      (node (ref "U7") (pin "A7") (pinfunction "DQ12_A7") (pintype "bidirectional"))
    )
    (net (code "97") (name "/PL_DDR_DQ61") (class "Default")
      (node (ref "U7") (pin "A2") (pinfunction "DQ13_A2") (pintype "bidirectional"))
    )
    (net (code "98") (name "/PL_DDR_DQ62") (class "Default")
      (node (ref "U7") (pin "B8") (pinfunction "DQ14_B8") (pintype "bidirectional"))
    )
    (net (code "99") (name "/PL_DDR_DQ63") (class "Default")
      (node (ref "U7") (pin "A3") (pinfunction "DQ15_A3") (pintype "bidirectional"))
    )
    (net (code "100") (name "/PL_DDR_DQ64") (class "Default")
      (node (ref "U8") (pin "E3") (pinfunction "DQ0_E3") (pintype "bidirectional"))
    )
    (net (code "101") (name "/PL_DDR_DQ65") (class "Default")
      (node (ref "U8") (pin "F7") (pinfunction "DQ1_F7") (pintype "bidirectional"))
    )
    (net (code "102") (name "/PL_DDR_DQ66") (class "Default")
      (node (ref "U8") (pin "F2") (pinfunction "DQ2_F2") (pintype "bidirectional"))
    )
    (net (code "103") (name "/PL_DDR_DQ67") (class "Default")
      (node (ref "U8") (pin "F8") (pinfunction "DQ3_F8") (pintype "bidirectional"))
    )
    (net (code "104") (name "/PL_DDR_DQ68") (class "Default")
      (node (ref "U8") (pin "H3") (pinfunction "DQ4_H3") (pintype "bidirectional"))
    )
    (net (code "105") (name "/PL_DDR_DQ69") (class "Default")
      (node (ref "U8") (pin "H8") (pinfunction "DQ5_H8") (pintype "bidirectional"))
    )
    (net (code "106") (name "/PL_DDR_DQ70") (class "Default")
      (node (ref "U8") (pin "G2") (pinfunction "DQ6_G2") (pintype "bidirectional"))
    )
    (net (code "107") (name "/PL_DDR_DQ71") (class "Default")
      (node (ref "U8") (pin "H7") (pinfunction "DQ7_H7") (pintype "bidirectional"))
    )
    (net (code "108") (name "/PL_DDR_DQS_Byte0_N") (class "Default")
      (node (ref "U4") (pin "G3") (pinfunction "~{LDQS}_G3") (pintype "bidirectional"))
    )
    (net (code "109") (name "/PL_DDR_DQS_Byte0_P") (class "Default")
      (node (ref "U4") (pin "F3") (pinfunction "LDQS_F3") (pintype "bidirectional"))
    )
    (net (code "110") (name "/PL_DDR_DQS_Byte1_N") (class "Default")
      (node (ref "U4") (pin "B7") (pinfunction "~{UDQS}_B7") (pintype "bidirectional"))
    )
    (net (code "111") (name "/PL_DDR_DQS_Byte1_P") (class "Default")
      (node (ref "U4") (pin "C7") (pinfunction "UDQS_C7") (pintype "bidirectional"))
    )
    (net (code "112") (name "/PL_DDR_DQS_Byte2_N") (class "Default")
      (node (ref "U5") (pin "G3") (pinfunction "~{LDQS}_G3") (pintype "bidirectional"))
    )
    (net (code "113") (name "/PL_DDR_DQS_Byte2_P") (class "Default")
      (node (ref "U5") (pin "F3") (pinfunction "LDQS_F3") (pintype "bidirectional"))
    )
    (net (code "114") (name "/PL_DDR_DQS_Byte3_N") (class "Default")
      (node (ref "U5") (pin "B7") (pinfunction "~{UDQS}_B7") (pintype "bidirectional"))
    )
    (net (code "115") (name "/PL_DDR_DQS_Byte3_P") (class "Default")
      (node (ref "U5") (pin "C7") (pinfunction "UDQS_C7") (pintype "bidirectional"))
    )
    (net (code "116") (name "/PL_DDR_DQS_Byte4_N") (class "Default")
      (node (ref "U6") (pin "F3") (pinfunction "LDQS_F3") (pintype "bidirectional"))
    )
    (net (code "117") (name "/PL_DDR_DQS_Byte4_P") (class "Default")
      (node (ref "U6") (pin "G3") (pinfunction "~{LDQS}_G3") (pintype "bidirectional"))
    )
    (net (code "118") (name "/PL_DDR_DQS_Byte5_N") (class "Default")
      (node (ref "U6") (pin "C7") (pinfunction "UDQS_C7") (pintype "bidirectional"))
    )
    (net (code "119") (name "/PL_DDR_DQS_Byte5_P") (class "Default")
      (node (ref "U6") (pin "B7") (pinfunction "~{UDQS}_B7") (pintype "bidirectional"))
    )
    (net (code "120") (name "/PL_DDR_DQS_Byte6_N") (class "Default")
      (node (ref "U7") (pin "F3") (pinfunction "LDQS_F3") (pintype "bidirectional"))
    )
    (net (code "121") (name "/PL_DDR_DQS_Byte6_P") (class "Default")
      (node (ref "U7") (pin "G3") (pinfunction "~{LDQS}_G3") (pintype "bidirectional"))
    )
    (net (code "122") (name "/PL_DDR_DQS_Byte7_N") (class "Default")
      (node (ref "U7") (pin "C7") (pinfunction "UDQS_C7") (pintype "bidirectional"))
    )
    (net (code "123") (name "/PL_DDR_DQS_Byte7_P") (class "Default")
      (node (ref "U7") (pin "B7") (pinfunction "~{UDQS}_B7") (pintype "bidirectional"))
    )
    (net (code "124") (name "/PL_DDR_DQS_Byte8_N") (class "Default")
      (node (ref "U8") (pin "G3") (pinfunction "~{LDQS}_G3") (pintype "bidirectional"))
    )
    (net (code "125") (name "/PL_DDR_DQS_Byte8_P") (class "Default")
      (node (ref "U8") (pin "F3") (pinfunction "LDQS_F3") (pintype "bidirectional"))
    )
    (net (code "126") (name "/PL_DDR_ODT") (class "Default")
      (node (ref "R36") (pin "1") (pinfunction "1_1") (pintype "passive"))
      (node (ref "U4") (pin "K1") (pinfunction "ODT_K1") (pintype "input"))
      (node (ref "U5") (pin "K1") (pinfunction "ODT_K1") (pintype "input"))
      (node (ref "U6") (pin "K1") (pinfunction "ODT_K1") (pintype "input"))
      (node (ref "U7") (pin "K1") (pinfunction "ODT_K1") (pintype "input"))
      (node (ref "U8") (pin "K1") (pinfunction "ODT_K1") (pintype "input"))
    )
    (net (code "127") (name "/PL_DDR_RAS") (class "Default")
      (node (ref "R37") (pin "1") (pinfunction "1_1") (pintype "passive"))
      (node (ref "U4") (pin "J3") (pinfunction "~{RAS}_J3") (pintype "input"))
      (node (ref "U5") (pin "J3") (pinfunction "~{RAS}_J3") (pintype "input"))
      (node (ref "U6") (pin "J3") (pinfunction "~{RAS}_J3") (pintype "input"))
      (node (ref "U7") (pin "J3") (pinfunction "~{RAS}_J3") (pintype "input"))
      (node (ref "U8") (pin "J3") (pinfunction "~{RAS}_J3") (pintype "input"))
    )
    (net (code "128") (name "/PL_DDR_RST") (class "Default")
      (node (ref "R59") (pin "1") (pinfunction "1_1") (pintype "passive"))
      (node (ref "U4") (pin "T2") (pinfunction "~{RESET}_T2") (pintype "input"))
      (node (ref "U5") (pin "T2") (pinfunction "~{RESET}_T2") (pintype "input"))
      (node (ref "U6") (pin "T2") (pinfunction "~{RESET}_T2") (pintype "input"))
      (node (ref "U7") (pin "T2") (pinfunction "~{RESET}_T2") (pintype "input"))
      (node (ref "U8") (pin "T2") (pinfunction "~{RESET}_T2") (pintype "input"))
    )
    (net (code "129") (name "/PL_DDR_WE") (class "Default")
      (node (ref "R38") (pin "1") (pinfunction "1_1") (pintype "passive"))
      (node (ref "U4") (pin "L3") (pinfunction "~{WE}_L3") (pintype "input"))
      (node (ref "U5") (pin "L3") (pinfunction "~{WE}_L3") (pintype "input"))
      (node (ref "U6") (pin "L3") (pinfunction "~{WE}_L3") (pintype "input"))
      (node (ref "U7") (pin "L3") (pinfunction "~{WE}_L3") (pintype "input"))
      (node (ref "U8") (pin "L3") (pinfunction "~{WE}_L3") (pintype "input"))
    )
    (net (code "130") (name "/PL_DDR_ZQ1") (class "Default")
      (node (ref "R28") (pin "1") (pinfunction "1_1") (pintype "passive"))
      (node (ref "U4") (pin "L8") (pinfunction "ZQ_L8") (pintype "passive"))
    )
    (net (code "131") (name "/PL_DDR_ZQ2") (class "Default")
      (node (ref "R29") (pin "1") (pinfunction "1_1") (pintype "passive"))
      (node (ref "U5") (pin "L8") (pinfunction "ZQ_L8") (pintype "passive"))
    )
    (net (code "132") (name "/PL_DDR_ZQ3") (class "Default")
      (node (ref "R30") (pin "1") (pinfunction "1_1") (pintype "passive"))
      (node (ref "U6") (pin "L8") (pinfunction "ZQ_L8") (pintype "passive"))
    )
    (net (code "133") (name "/PL_DDR_ZQ4") (class "Default")
      (node (ref "R31") (pin "1") (pinfunction "1_1") (pintype "passive"))
      (node (ref "U7") (pin "L8") (pinfunction "ZQ_L8") (pintype "passive"))
    )
    (net (code "134") (name "/PL_DDR_ZQ5") (class "Default")
      (node (ref "R32") (pin "1") (pinfunction "1_1") (pintype "passive"))
      (node (ref "U8") (pin "L8") (pinfunction "ZQ_L8") (pintype "passive"))
    )
    (net (code "137") (name "GND") (class "Default")
      (node (ref "C12") (pin "1") (pinfunction "1_1") (pintype "passive"))
      (node (ref "C13") (pin "1") (pinfunction "1_1") (pintype "passive"))
      (node (ref "C14") (pin "1") (pinfunction "1_1") (pintype "passive"))
      (node (ref "C15") (pin "1") (pinfunction "1_1") (pintype "passive"))
      (node (ref "C16") (pin "1") (pinfunction "1_1") (pintype "passive"))
      (node (ref "C17") (pin "1") (pinfunction "1_1") (pintype "passive"))
      (node (ref "C18") (pin "1") (pinfunction "1_1") (pintype "passive"))
      (node (ref "C20") (pin "1") (pinfunction "1_1") (pintype "passive"))
      (node (ref "C21") (pin "2") (pinfunction "2_2") (pintype "passive"))
      (node (ref "C22") (pin "1") (pinfunction "1_1") (pintype "passive"))
      (node (ref "C23") (pin "1") (pinfunction "1_1") (pintype "passive"))
      (node (ref "C24") (pin "1") (pinfunction "1_1") (pintype "passive"))
      (node (ref "C25") (pin "1") (pinfunction "1_1") (pintype "passive"))
      (node (ref "R28") (pin "2") (pinfunction "2_2") (pintype "passive"))
      (node (ref "R29") (pin "2") (pinfunction "2_2") (pintype "passive"))
      (node (ref "R30") (pin "2") (pinfunction "2_2") (pintype "passive"))
      (node (ref "R31") (pin "2") (pinfunction "2_2") (pintype "passive"))
      (node (ref "R32") (pin "2") (pinfunction "2_2") (pintype "passive"))
      (node (ref "R59") (pin "2") (pinfunction "2_2") (pintype "passive"))
      (node (ref "U4") (pin "A9") (pinfunction "VSS_A9") (pintype "power_in"))
      (node (ref "U4") (pin "B1") (pinfunction "VSSQ_B1") (pintype "power_in"))
      (node (ref "U4") (pin "B3") (pinfunction "VSS_B3") (pintype "power_in"))
      (node (ref "U4") (pin "B9") (pinfunction "VSSQ_B9") (pintype "power_in"))
      (node (ref "U4") (pin "D1") (pinfunction "VSSQ_D1") (pintype "power_in"))
      (node (ref "U4") (pin "D8") (pinfunction "VSSQ_D8") (pintype "power_in"))
      (node (ref "U4") (pin "E1") (pinfunction "VSS_E1") (pintype "power_in"))
      (node (ref "U4") (pin "E2") (pinfunction "VSSQ_E2") (pintype "power_in"))
      (node (ref "U4") (pin "E8") (pinfunction "VSSQ_E8") (pintype "power_in"))
      (node (ref "U4") (pin "F9") (pinfunction "VSSQ_F9") (pintype "power_in"))
      (node (ref "U4") (pin "G1") (pinfunction "VSSQ_G1") (pintype "power_in"))
      (node (ref "U4") (pin "G8") (pinfunction "VSS_G8") (pintype "power_in"))
      (node (ref "U4") (pin "G9") (pinfunction "VSSQ_G9") (pintype "power_in"))
      (node (ref "U4") (pin "J2") (pinfunction "VSS_J2") (pintype "power_in"))
      (node (ref "U4") (pin "J8") (pinfunction "VSS_J8") (pintype "power_in"))
      (node (ref "U4") (pin "M1") (pinfunction "VSS_M1") (pintype "power_in"))
      (node (ref "U4") (pin "M9") (pinfunction "VSS_M9") (pintype "power_in"))
      (node (ref "U4") (pin "P1") (pinfunction "VSS_P1") (pintype "power_in"))
      (node (ref "U4") (pin "P9") (pinfunction "VSS_P9") (pintype "power_in"))
      (node (ref "U4") (pin "T1") (pinfunction "VSS_T1") (pintype "power_in"))
      (node (ref "U4") (pin "T9") (pinfunction "VSS_T9") (pintype "power_in"))
      (node (ref "U5") (pin "A9") (pinfunction "VSS_A9") (pintype "power_in"))
      (node (ref "U5") (pin "B1") (pinfunction "VSSQ_B1") (pintype "power_in"))
      (node (ref "U5") (pin "B3") (pinfunction "VSS_B3") (pintype "power_in"))
      (node (ref "U5") (pin "B9") (pinfunction "VSSQ_B9") (pintype "power_in"))
      (node (ref "U5") (pin "D1") (pinfunction "VSSQ_D1") (pintype "power_in"))
      (node (ref "U5") (pin "D8") (pinfunction "VSSQ_D8") (pintype "power_in"))
      (node (ref "U5") (pin "E1") (pinfunction "VSS_E1") (pintype "power_in"))
      (node (ref "U5") (pin "E2") (pinfunction "VSSQ_E2") (pintype "power_in"))
      (node (ref "U5") (pin "E8") (pinfunction "VSSQ_E8") (pintype "power_in"))
      (node (ref "U5") (pin "F9") (pinfunction "VSSQ_F9") (pintype "power_in"))
      (node (ref "U5") (pin "G1") (pinfunction "VSSQ_G1") (pintype "power_in"))
      (node (ref "U5") (pin "G8") (pinfunction "VSS_G8") (pintype "power_in"))
      (node (ref "U5") (pin "G9") (pinfunction "VSSQ_G9") (pintype "power_in"))
      (node (ref "U5") (pin "J2") (pinfunction "VSS_J2") (pintype "power_in"))
      (node (ref "U5") (pin "J8") (pinfunction "VSS_J8") (pintype "power_in"))
      (node (ref "U5") (pin "M1") (pinfunction "VSS_M1") (pintype "power_in"))
      (node (ref "U5") (pin "M9") (pinfunction "VSS_M9") (pintype "power_in"))
      (node (ref "U5") (pin "P1") (pinfunction "VSS_P1") (pintype "power_in"))
      (node (ref "U5") (pin "P9") (pinfunction "VSS_P9") (pintype "power_in"))
      (node (ref "U5") (pin "T1") (pinfunction "VSS_T1") (pintype "power_in"))
      (node (ref "U5") (pin "T9") (pinfunction "VSS_T9") (pintype "power_in"))
      (node (ref "U6") (pin "A9") (pinfunction "VSS_A9") (pintype "power_in"))
      (node (ref "U6") (pin "B1") (pinfunction "VSSQ_B1") (pintype "power_in"))
      (node (ref "U6") (pin "B3") (pinfunction "VSS_B3") (pintype "power_in"))
      (node (ref "U6") (pin "B9") (pinfunction "VSSQ_B9") (pintype "power_in"))
      (node (ref "U6") (pin "D1") (pinfunction "VSSQ_D1") (pintype "power_in"))
      (node (ref "U6") (pin "D8") (pinfunction "VSSQ_D8") (pintype "power_in"))
      (node (ref "U6") (pin "E1") (pinfunction "VSS_E1") (pintype "power_in"))
      (node (ref "U6") (pin "E2") (pinfunction "VSSQ_E2") (pintype "power_in"))
      (node (ref "U6") (pin "E8") (pinfunction "VSSQ_E8") (pintype "power_in"))
      (node (ref "U6") (pin "F9") (pinfunction "VSSQ_F9") (pintype "power_in"))
      (node (ref "U6") (pin "G1") (pinfunction "VSSQ_G1") (pintype "power_in"))
      (node (ref "U6") (pin "G8") (pinfunction "VSS_G8") (pintype "power_in"))
      (node (ref "U6") (pin "G9") (pinfunction "VSSQ_G9") (pintype "power_in"))
      (node (ref "U6") (pin "J2") (pinfunction "VSS_J2") (pintype "power_in"))
      (node (ref "U6") (pin "J8") (pinfunction "VSS_J8") (pintype "power_in"))
      (node (ref "U6") (pin "M1") (pinfunction "VSS_M1") (pintype "power_in"))
      (node (ref "U6") (pin "M9") (pinfunction "VSS_M9") (pintype "power_in"))
      (node (ref "U6") (pin "P1") (pinfunction "VSS_P1") (pintype "power_in"))
      (node (ref "U6") (pin "P9") (pinfunction "VSS_P9") (pintype "power_in"))
      (node (ref "U6") (pin "T1") (pinfunction "VSS_T1") (pintype "power_in"))
      (node (ref "U6") (pin "T9") (pinfunction "VSS_T9") (pintype "power_in"))
      (node (ref "U7") (pin "A9") (pinfunction "VSS_A9") (pintype "power_in"))
      (node (ref "U7") (pin "B1") (pinfunction "VSSQ_B1") (pintype "power_in"))
      (node (ref "U7") (pin "B3") (pinfunction "VSS_B3") (pintype "power_in"))
      (node (ref "U7") (pin "B9") (pinfunction "VSSQ_B9") (pintype "power_in"))
      (node (ref "U7") (pin "D1") (pinfunction "VSSQ_D1") (pintype "power_in"))
      (node (ref "U7") (pin "D8") (pinfunction "VSSQ_D8") (pintype "power_in"))
      (node (ref "U7") (pin "E1") (pinfunction "VSS_E1") (pintype "power_in"))
      (node (ref "U7") (pin "E2") (pinfunction "VSSQ_E2") (pintype "power_in"))
      (node (ref "U7") (pin "E8") (pinfunction "VSSQ_E8") (pintype "power_in"))
      (node (ref "U7") (pin "F9") (pinfunction "VSSQ_F9") (pintype "power_in"))
      (node (ref "U7") (pin "G1") (pinfunction "VSSQ_G1") (pintype "power_in"))
      (node (ref "U7") (pin "G8") (pinfunction "VSS_G8") (pintype "power_in"))
      (node (ref "U7") (pin "G9") (pinfunction "VSSQ_G9") (pintype "power_in"))
      (node (ref "U7") (pin "J2") (pinfunction "VSS_J2") (pintype "power_in"))
      (node (ref "U7") (pin "J8") (pinfunction "VSS_J8") (pintype "power_in"))
      (node (ref "U7") (pin "M1") (pinfunction "VSS_M1") (pintype "power_in"))
      (node (ref "U7") (pin "M9") (pinfunction "VSS_M9") (pintype "power_in"))
      (node (ref "U7") (pin "P1") (pinfunction "VSS_P1") (pintype "power_in"))
      (node (ref "U7") (pin "P9") (pinfunction "VSS_P9") (pintype "power_in"))
      (node (ref "U7") (pin "T1") (pinfunction "VSS_T1") (pintype "power_in"))
      (node (ref "U7") (pin "T9") (pinfunction "VSS_T9") (pintype "power_in"))
      (node (ref "U8") (pin "A9") (pinfunction "VSS_A9") (pintype "power_in"))
      (node (ref "U8") (pin "B1") (pinfunction "VSSQ_B1") (pintype "power_in"))
      (node (ref "U8") (pin "B3") (pinfunction "VSS_B3") (pintype "power_in"))
      (node (ref "U8") (pin "B9") (pinfunction "VSSQ_B9") (pintype "power_in"))
      (node (ref "U8") (pin "D1") (pinfunction "VSSQ_D1") (pintype "power_in"))
      (node (ref "U8") (pin "D8") (pinfunction "VSSQ_D8") (pintype "power_in"))
      (node (ref "U8") (pin "E1") (pinfunction "VSS_E1") (pintype "power_in"))
      (node (ref "U8") (pin "E2") (pinfunction "VSSQ_E2") (pintype "power_in"))
      (node (ref "U8") (pin "E8") (pinfunction "VSSQ_E8") (pintype "power_in"))
      (node (ref "U8") (pin "F9") (pinfunction "VSSQ_F9") (pintype "power_in"))
      (node (ref "U8") (pin "G1") (pinfunction "VSSQ_G1") (pintype "power_in"))
      (node (ref "U8") (pin "G8") (pinfunction "VSS_G8") (pintype "power_in"))
      (node (ref "U8") (pin "G9") (pinfunction "VSSQ_G9") (pintype "power_in"))
      (node (ref "U8") (pin "J2") (pinfunction "VSS_J2") (pintype "power_in"))
      (node (ref "U8") (pin "J8") (pinfunction "VSS_J8") (pintype "power_in"))
      (node (ref "U8") (pin "M1") (pinfunction "VSS_M1") (pintype "power_in"))
      (node (ref "U8") (pin "M9") (pinfunction "VSS_M9") (pintype "power_in"))
      (node (ref "U8") (pin "P1") (pinfunction "VSS_P1") (pintype "power_in"))
      (node (ref "U8") (pin "P9") (pinfunction "VSS_P9") (pintype "power_in"))
      (node (ref "U8") (pin "T1") (pinfunction "VSS_T1") (pintype "power_in"))
      (node (ref "U8") (pin "T9") (pinfunction "VSS_T9") (pintype "power_in"))
    )
    (net (code "138") (name "VCCO_PL_DDR") (class "Default")
      (node (ref "C19") (pin "2") (pinfunction "2_2") (pintype "passive"))
      (node (ref "U4") (pin "A1") (pinfunction "VDDQ_A1") (pintype "power_in"))
      (node (ref "U4") (pin "A8") (pinfunction "VDDQ_A8") (pintype "power_in"))
      (node (ref "U4") (pin "B2") (pinfunction "VDD_B2") (pintype "power_in"))
      (node (ref "U4") (pin "C1") (pinfunction "VDDQ_C1") (pintype "power_in"))
      (node (ref "U4") (pin "C9") (pinfunction "VDDQ_C9") (pintype "power_in"))
      (node (ref "U4") (pin "D2") (pinfunction "VDDQ_D2") (pintype "power_in"))
      (node (ref "U4") (pin "D9") (pinfunction "VDD_D9") (pintype "power_in"))
      (node (ref "U4") (pin "E9") (pinfunction "VDDQ_E9") (pintype "power_in"))
      (node (ref "U4") (pin "F1") (pinfunction "VDDQ_F1") (pintype "power_in"))
      (node (ref "U4") (pin "G7") (pinfunction "VDD_G7") (pintype "power_in"))
      (node (ref "U4") (pin "H2") (pinfunction "VDDQ_H2") (pintype "power_in"))
      (node (ref "U4") (pin "H9") (pinfunction "VDDQ_H9") (pintype "power_in"))
      (node (ref "U4") (pin "K2") (pinfunction "VDD_K2") (pintype "power_in"))
      (node (ref "U4") (pin "K8") (pinfunction "VDD_K8") (pintype "power_in"))
      (node (ref "U4") (pin "N1") (pinfunction "VDD_N1") (pintype "power_in"))
      (node (ref "U4") (pin "N9") (pinfunction "VDD_N9") (pintype "power_in"))
      (node (ref "U4") (pin "R1") (pinfunction "VDD_R1") (pintype "power_in"))
      (node (ref "U4") (pin "R9") (pinfunction "VDD_R9") (pintype "power_in"))
      (node (ref "U5") (pin "A1") (pinfunction "VDDQ_A1") (pintype "power_in"))
      (node (ref "U5") (pin "A8") (pinfunction "VDDQ_A8") (pintype "power_in"))
      (node (ref "U5") (pin "B2") (pinfunction "VDD_B2") (pintype "power_in"))
      (node (ref "U5") (pin "C1") (pinfunction "VDDQ_C1") (pintype "power_in"))
      (node (ref "U5") (pin "C9") (pinfunction "VDDQ_C9") (pintype "power_in"))
      (node (ref "U5") (pin "D2") (pinfunction "VDDQ_D2") (pintype "power_in"))
      (node (ref "U5") (pin "D9") (pinfunction "VDD_D9") (pintype "power_in"))
      (node (ref "U5") (pin "E9") (pinfunction "VDDQ_E9") (pintype "power_in"))
      (node (ref "U5") (pin "F1") (pinfunction "VDDQ_F1") (pintype "power_in"))
      (node (ref "U5") (pin "G7") (pinfunction "VDD_G7") (pintype "power_in"))
      (node (ref "U5") (pin "H2") (pinfunction "VDDQ_H2") (pintype "power_in"))
      (node (ref "U5") (pin "H9") (pinfunction "VDDQ_H9") (pintype "power_in"))
      (node (ref "U5") (pin "K2") (pinfunction "VDD_K2") (pintype "power_in"))
      (node (ref "U5") (pin "K8") (pinfunction "VDD_K8") (pintype "power_in"))
      (node (ref "U5") (pin "N1") (pinfunction "VDD_N1") (pintype "power_in"))
      (node (ref "U5") (pin "N9") (pinfunction "VDD_N9") (pintype "power_in"))
      (node (ref "U5") (pin "R1") (pinfunction "VDD_R1") (pintype "power_in"))
      (node (ref "U5") (pin "R9") (pinfunction "VDD_R9") (pintype "power_in"))
      (node (ref "U6") (pin "A1") (pinfunction "VDDQ_A1") (pintype "power_in"))
      (node (ref "U6") (pin "A8") (pinfunction "VDDQ_A8") (pintype "power_in"))
      (node (ref "U6") (pin "B2") (pinfunction "VDD_B2") (pintype "power_in"))
      (node (ref "U6") (pin "C1") (pinfunction "VDDQ_C1") (pintype "power_in"))
      (node (ref "U6") (pin "C9") (pinfunction "VDDQ_C9") (pintype "power_in"))
      (node (ref "U6") (pin "D2") (pinfunction "VDDQ_D2") (pintype "power_in"))
      (node (ref "U6") (pin "D9") (pinfunction "VDD_D9") (pintype "power_in"))
      (node (ref "U6") (pin "E9") (pinfunction "VDDQ_E9") (pintype "power_in"))
      (node (ref "U6") (pin "F1") (pinfunction "VDDQ_F1") (pintype "power_in"))
      (node (ref "U6") (pin "G7") (pinfunction "VDD_G7") (pintype "power_in"))
      (node (ref "U6") (pin "H2") (pinfunction "VDDQ_H2") (pintype "power_in"))
      (node (ref "U6") (pin "H9") (pinfunction "VDDQ_H9") (pintype "power_in"))
      (node (ref "U6") (pin "K2") (pinfunction "VDD_K2") (pintype "power_in"))
      (node (ref "U6") (pin "K8") (pinfunction "VDD_K8") (pintype "power_in"))
      (node (ref "U6") (pin "N1") (pinfunction "VDD_N1") (pintype "power_in"))
      (node (ref "U6") (pin "N9") (pinfunction "VDD_N9") (pintype "power_in"))
      (node (ref "U6") (pin "R1") (pinfunction "VDD_R1") (pintype "power_in"))
      (node (ref "U6") (pin "R9") (pinfunction "VDD_R9") (pintype "power_in"))
      (node (ref "U7") (pin "A1") (pinfunction "VDDQ_A1") (pintype "power_in"))
      (node (ref "U7") (pin "A8") (pinfunction "VDDQ_A8") (pintype "power_in"))
      (node (ref "U7") (pin "B2") (pinfunction "VDD_B2") (pintype "power_in"))
      (node (ref "U7") (pin "C1") (pinfunction "VDDQ_C1") (pintype "power_in"))
      (node (ref "U7") (pin "C9") (pinfunction "VDDQ_C9") (pintype "power_in"))
      (node (ref "U7") (pin "D2") (pinfunction "VDDQ_D2") (pintype "power_in"))
      (node (ref "U7") (pin "D9") (pinfunction "VDD_D9") (pintype "power_in"))
      (node (ref "U7") (pin "E9") (pinfunction "VDDQ_E9") (pintype "power_in"))
      (node (ref "U7") (pin "F1") (pinfunction "VDDQ_F1") (pintype "power_in"))
      (node (ref "U7") (pin "G7") (pinfunction "VDD_G7") (pintype "power_in"))
      (node (ref "U7") (pin "H2") (pinfunction "VDDQ_H2") (pintype "power_in"))
      (node (ref "U7") (pin "H9") (pinfunction "VDDQ_H9") (pintype "power_in"))
      (node (ref "U7") (pin "K2") (pinfunction "VDD_K2") (pintype "power_in"))
      (node (ref "U7") (pin "K8") (pinfunction "VDD_K8") (pintype "power_in"))
      (node (ref "U7") (pin "N1") (pinfunction "VDD_N1") (pintype "power_in"))
      (node (ref "U7") (pin "N9") (pinfunction "VDD_N9") (pintype "power_in"))
      (node (ref "U7") (pin "R1") (pinfunction "VDD_R1") (pintype "power_in"))
      (node (ref "U7") (pin "R9") (pinfunction "VDD_R9") (pintype "power_in"))
      (node (ref "U8") (pin "A1") (pinfunction "VDDQ_A1") (pintype "power_in"))
      (node (ref "U8") (pin "A8") (pinfunction "VDDQ_A8") (pintype "power_in"))
      (node (ref "U8") (pin "B2") (pinfunction "VDD_B2") (pintype "power_in"))
      (node (ref "U8") (pin "C1") (pinfunction "VDDQ_C1") (pintype "power_in"))
      (node (ref "U8") (pin "C9") (pinfunction "VDDQ_C9") (pintype "power_in"))
      (node (ref "U8") (pin "D2") (pinfunction "VDDQ_D2") (pintype "power_in"))
      (node (ref "U8") (pin "D9") (pinfunction "VDD_D9") (pintype "power_in"))
      (node (ref "U8") (pin "E9") (pinfunction "VDDQ_E9") (pintype "power_in"))
      (node (ref "U8") (pin "F1") (pinfunction "VDDQ_F1") (pintype "power_in"))
      (node (ref "U8") (pin "G7") (pinfunction "VDD_G7") (pintype "power_in"))
      (node (ref "U8") (pin "H2") (pinfunction "VDDQ_H2") (pintype "power_in"))
      (node (ref "U8") (pin "H9") (pinfunction "VDDQ_H9") (pintype "power_in"))
      (node (ref "U8") (pin "K2") (pinfunction "VDD_K2") (pintype "power_in"))
      (node (ref "U8") (pin "K8") (pinfunction "VDD_K8") (pintype "power_in"))
      (node (ref "U8") (pin "N1") (pinfunction "VDD_N1") (pintype "power_in"))
      (node (ref "U8") (pin "N9") (pinfunction "VDD_N9") (pintype "power_in"))
      (node (ref "U8") (pin "R1") (pinfunction "VDD_R1") (pintype "power_in"))
      (node (ref "U8") (pin "R9") (pinfunction "VDD_R9") (pintype "power_in"))
    )
    (net (code "139") (name "VTT_PL_DDR") (class "Default")
      (node (ref "C17") (pin "2") (pinfunction "2_2") (pintype "passive"))
      (node (ref "C18") (pin "2") (pinfunction "2_2") (pintype "passive"))
      (node (ref "C20") (pin "2") (pinfunction "2_2") (pintype "passive"))
      (node (ref "C21") (pin "1") (pinfunction "1_1") (pintype "passive"))
      (node (ref "C22") (pin "2") (pinfunction "2_2") (pintype "passive"))
      (node (ref "C23") (pin "2") (pinfunction "2_2") (pintype "passive"))
      (node (ref "C24") (pin "2") (pinfunction "2_2") (pintype "passive"))
      (node (ref "C25") (pin "2") (pinfunction "2_2") (pintype "passive"))
      (node (ref "R33") (pin "2") (pinfunction "2_2") (pintype "passive"))
      (node (ref "R34") (pin "2") (pinfunction "2_2") (pintype "passive"))
      (node (ref "R35") (pin "2") (pinfunction "2_2") (pintype "passive"))
      (node (ref "R36") (pin "2") (pinfunction "2_2") (pintype "passive"))
      (node (ref "R37") (pin "2") (pinfunction "2_2") (pintype "passive"))
      (node (ref "R38") (pin "2") (pinfunction "2_2") (pintype "passive"))
      (node (ref "R39") (pin "2") (pinfunction "2_2") (pintype "passive"))
      (node (ref "R40") (pin "2") (pinfunction "2_2") (pintype "passive"))
      (node (ref "R41") (pin "2") (pinfunction "2_2") (pintype "passive"))
      (node (ref "R42") (pin "2") (pinfunction "2_2") (pintype "passive"))
      (node (ref "R43") (pin "2") (pinfunction "2_2") (pintype "passive"))
      (node (ref "R44") (pin "2") (pinfunction "2_2") (pintype "passive"))
      (node (ref "R45") (pin "2") (pinfunction "2_2") (pintype "passive"))
      (node (ref "R46") (pin "2") (pinfunction "2_2") (pintype "passive"))
      (node (ref "R47") (pin "2") (pinfunction "2_2") (pintype "passive"))
      (node (ref "R48") (pin "2") (pinfunction "2_2") (pintype "passive"))
      (node (ref "R49") (pin "2") (pinfunction "2_2") (pintype "passive"))
      (node (ref "R50") (pin "2") (pinfunction "2_2") (pintype "passive"))
      (node (ref "R51") (pin "2") (pinfunction "2_2") (pintype "passive"))
      (node (ref "R52") (pin "2") (pinfunction "2_2") (pintype "passive"))
      (node (ref "R54") (pin "2") (pinfunction "2_2") (pintype "passive"))
      (node (ref "R55") (pin "2") (pinfunction "2_2") (pintype "passive"))
      (node (ref "R56") (pin "2") (pinfunction "2_2") (pintype "passive"))
      (node (ref "R58") (pin "2") (pinfunction "2_2") (pintype "passive"))
    )
    (net (code "140") (name "VTT_PL_REF") (class "Default")
      (node (ref "C12") (pin "2") (pinfunction "2_2") (pintype "passive"))
      (node (ref "C13") (pin "2") (pinfunction "2_2") (pintype "passive"))
      (node (ref "C14") (pin "2") (pinfunction "2_2") (pintype "passive"))
      (node (ref "C15") (pin "2") (pinfunction "2_2") (pintype "passive"))
      (node (ref "C16") (pin "2") (pinfunction "2_2") (pintype "passive"))
      (node (ref "U4") (pin "H1") (pinfunction "VREFDQ_H1") (pintype "power_in"))
      (node (ref "U4") (pin "M8") (pinfunction "VREFCA_M8") (pintype "power_in"))
      (node (ref "U5") (pin "H1") (pinfunction "VREFDQ_H1") (pintype "power_in"))
      (node (ref "U5") (pin "M8") (pinfunction "VREFCA_M8") (pintype "power_in"))
      (node (ref "U6") (pin "H1") (pinfunction "VREFDQ_H1") (pintype "power_in"))
      (node (ref "U6") (pin "M8") (pinfunction "VREFCA_M8") (pintype "power_in"))
      (node (ref "U7") (pin "H1") (pinfunction "VREFDQ_H1") (pintype "power_in"))
      (node (ref "U7") (pin "M8") (pinfunction "VREFCA_M8") (pintype "power_in"))
      (node (ref "U8") (pin "H1") (pinfunction "VREFDQ_H1") (pintype "power_in"))
      (node (ref "U8") (pin "M8") (pinfunction "VREFCA_M8") (pintype "power_in"))
    )
    (net (code "141") (name "unconnected-(U4A-NC-PadJ1)") (class "Default")
      (node (ref "U4") (pin "J1") (pinfunction "NC_J1") (pintype "passive+no_connect"))
    )
    (net (code "142") (name "unconnected-(U4A-NC-PadJ9)") (class "Default")
      (node (ref "U4") (pin "J9") (pinfunction "NC_J9") (pintype "passive+no_connect"))
    )
    (net (code "143") (name "unconnected-(U4A-NC-PadL1)") (class "Default")
      (node (ref "U4") (pin "L1") (pinfunction "NC_L1") (pintype "passive+no_connect"))
    )
    (net (code "144") (name "unconnected-(U4A-NC-PadL9)") (class "Default")
      (node (ref "U4") (pin "L9") (pinfunction "NC_L9") (pintype "passive+no_connect"))
    )
    (net (code "145") (name "unconnected-(U4A-NC-PadM7)") (class "Default")
      (node (ref "U4") (pin "M7") (pinfunction "NC_M7") (pintype "passive+no_connect"))
    )
    (net (code "146") (name "unconnected-(U5A-NC-PadJ1)") (class "Default")
      (node (ref "U5") (pin "J1") (pinfunction "NC_J1") (pintype "passive+no_connect"))
    )
    (net (code "147") (name "unconnected-(U5A-NC-PadJ9)") (class "Default")
      (node (ref "U5") (pin "J9") (pinfunction "NC_J9") (pintype "passive+no_connect"))
    )
    (net (code "148") (name "unconnected-(U5A-NC-PadL1)") (class "Default")
      (node (ref "U5") (pin "L1") (pinfunction "NC_L1") (pintype "passive+no_connect"))
    )
    (net (code "149") (name "unconnected-(U5A-NC-PadL9)") (class "Default")
      (node (ref "U5") (pin "L9") (pinfunction "NC_L9") (pintype "passive+no_connect"))
    )
    (net (code "150") (name "unconnected-(U5A-NC-PadM7)") (class "Default")
      (node (ref "U5") (pin "M7") (pinfunction "NC_M7") (pintype "passive+no_connect"))
    )
    (net (code "151") (name "unconnected-(U6A-NC-PadJ1)") (class "Default")
      (node (ref "U6") (pin "J1") (pinfunction "NC_J1") (pintype "passive+no_connect"))
    )
    (net (code "152") (name "unconnected-(U6A-NC-PadJ9)") (class "Default")
      (node (ref "U6") (pin "J9") (pinfunction "NC_J9") (pintype "passive+no_connect"))
    )
    (net (code "153") (name "unconnected-(U6A-NC-PadL1)") (class "Default")
      (node (ref "U6") (pin "L1") (pinfunction "NC_L1") (pintype "passive+no_connect"))
    )
    (net (code "154") (name "unconnected-(U6A-NC-PadL9)") (class "Default")
      (node (ref "U6") (pin "L9") (pinfunction "NC_L9") (pintype "passive+no_connect"))
    )
    (net (code "155") (name "unconnected-(U6A-NC-PadM7)") (class "Default")
      (node (ref "U6") (pin "M7") (pinfunction "NC_M7") (pintype "passive+no_connect"))
    )
    (net (code "156") (name "unconnected-(U7A-NC-PadJ1)") (class "Default")
      (node (ref "U7") (pin "J1") (pinfunction "NC_J1") (pintype "passive+no_connect"))
    )
    (net (code "157") (name "unconnected-(U7A-NC-PadJ9)") (class "Default")
      (node (ref "U7") (pin "J9") (pinfunction "NC_J9") (pintype "passive+no_connect"))
    )
    (net (code "158") (name "unconnected-(U7A-NC-PadL1)") (class "Default")
      (node (ref "U7") (pin "L1") (pinfunction "NC_L1") (pintype "passive+no_connect"))
    )
    (net (code "159") (name "unconnected-(U7A-NC-PadL9)") (class "Default")
      (node (ref "U7") (pin "L9") (pinfunction "NC_L9") (pintype "passive+no_connect"))
    )
    (net (code "160") (name "unconnected-(U7A-NC-PadM7)") (class "Default")
      (node (ref "U7") (pin "M7") (pinfunction "NC_M7") (pintype "passive+no_connect"))
    )
    (net (code "161") (name "unconnected-(U8A-DQ8-PadD7)") (class "Default")
      (node (ref "U8") (pin "D7") (pinfunction "DQ8_D7") (pintype "bidirectional+no_connect"))
    )
    (net (code "162") (name "unconnected-(U8A-DQ9-PadC3)") (class "Default")
      (node (ref "U8") (pin "C3") (pinfunction "DQ9_C3") (pintype "bidirectional+no_connect"))
    )
    (net (code "163") (name "unconnected-(U8A-DQ10-PadC8)") (class "Default")
      (node (ref "U8") (pin "C8") (pinfunction "DQ10_C8") (pintype "bidirectional+no_connect"))
    )
    (net (code "164") (name "unconnected-(U8A-DQ11-PadC2)") (class "Default")
      (node (ref "U8") (pin "C2") (pinfunction "DQ11_C2") (pintype "bidirectional+no_connect"))
    )
    (net (code "165") (name "unconnected-(U8A-DQ12-PadA7)") (class "Default")
      (node (ref "U8") (pin "A7") (pinfunction "DQ12_A7") (pintype "bidirectional+no_connect"))
    )
    (net (code "166") (name "unconnected-(U8A-DQ13-PadA2)") (class "Default")
      (node (ref "U8") (pin "A2") (pinfunction "DQ13_A2") (pintype "bidirectional+no_connect"))
    )
    (net (code "167") (name "unconnected-(U8A-DQ14-PadB8)") (class "Default")
      (node (ref "U8") (pin "B8") (pinfunction "DQ14_B8") (pintype "bidirectional+no_connect"))
    )
    (net (code "168") (name "unconnected-(U8A-DQ15-PadA3)") (class "Default")
      (node (ref "U8") (pin "A3") (pinfunction "DQ15_A3") (pintype "bidirectional+no_connect"))
    )
    (net (code "169") (name "unconnected-(U8A-NC-PadJ1)") (class "Default")
      (node (ref "U8") (pin "J1") (pinfunction "NC_J1") (pintype "passive+no_connect"))
    )
    (net (code "170") (name "unconnected-(U8A-NC-PadJ9)") (class "Default")
      (node (ref "U8") (pin "J9") (pinfunction "NC_J9") (pintype "passive+no_connect"))
    )
    (net (code "171") (name "unconnected-(U8A-NC-PadL1)") (class "Default")
      (node (ref "U8") (pin "L1") (pinfunction "NC_L1") (pintype "passive+no_connect"))
    )
    (net (code "172") (name "unconnected-(U8A-NC-PadL9)") (class "Default")
      (node (ref "U8") (pin "L9") (pinfunction "NC_L9") (pintype "passive+no_connect"))
    )
    (net (code "173") (name "unconnected-(U8A-NC-PadM7)") (class "Default")
      (node (ref "U8") (pin "M7") (pinfunction "NC_M7") (pintype "passive+no_connect"))
    )
    (net (code "174") (name "unconnected-(U8A-UDM-PadD3)") (class "Default")
      (node (ref "U8") (pin "D3") (pinfunction "UDM_D3") (pintype "input+no_connect"))
    )
    (net (code "175") (name "unconnected-(U8A-UDQS-PadC7)") (class "Default")
      (node (ref "U8") (pin "C7") (pinfunction "UDQS_C7") (pintype "bidirectional+no_connect"))
    )
    (net (code "176") (name "unconnected-(U8A-~{UDQS}-PadB7)") (class "Default")
      (node (ref "U8") (pin "B7") (pinfunction "~{UDQS}_B7") (pintype "bidirectional+no_connect"))
    )
  )
)
